# io-board-c-3.net
KiCad netlist of a schematic drawn in EAGLE
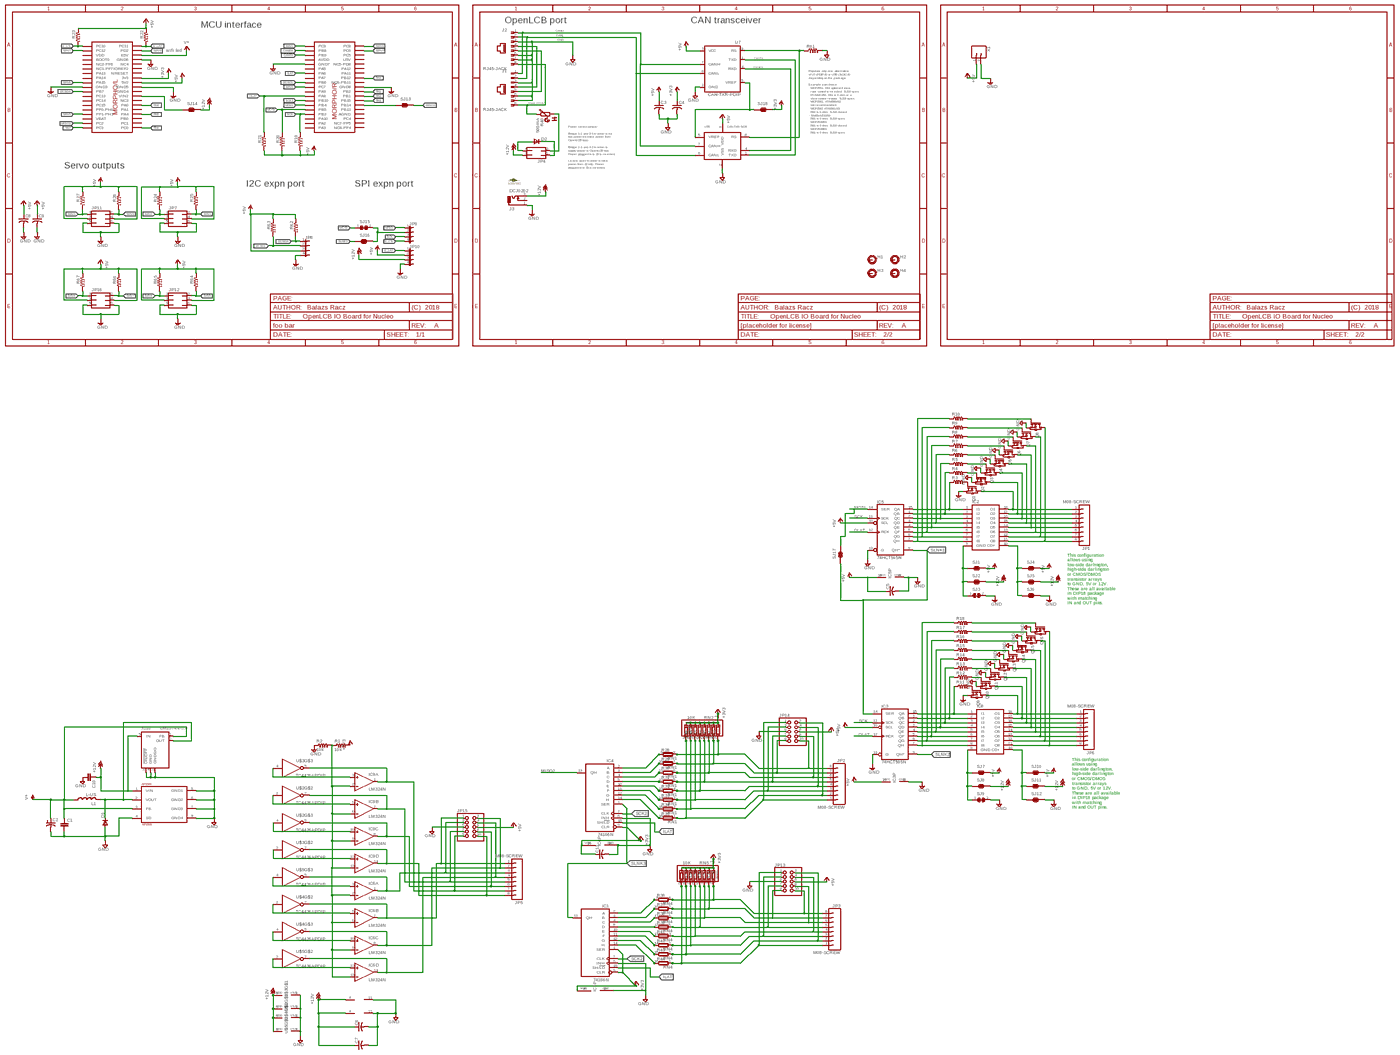
[diagram p0: schematic, sheet 1, overview]
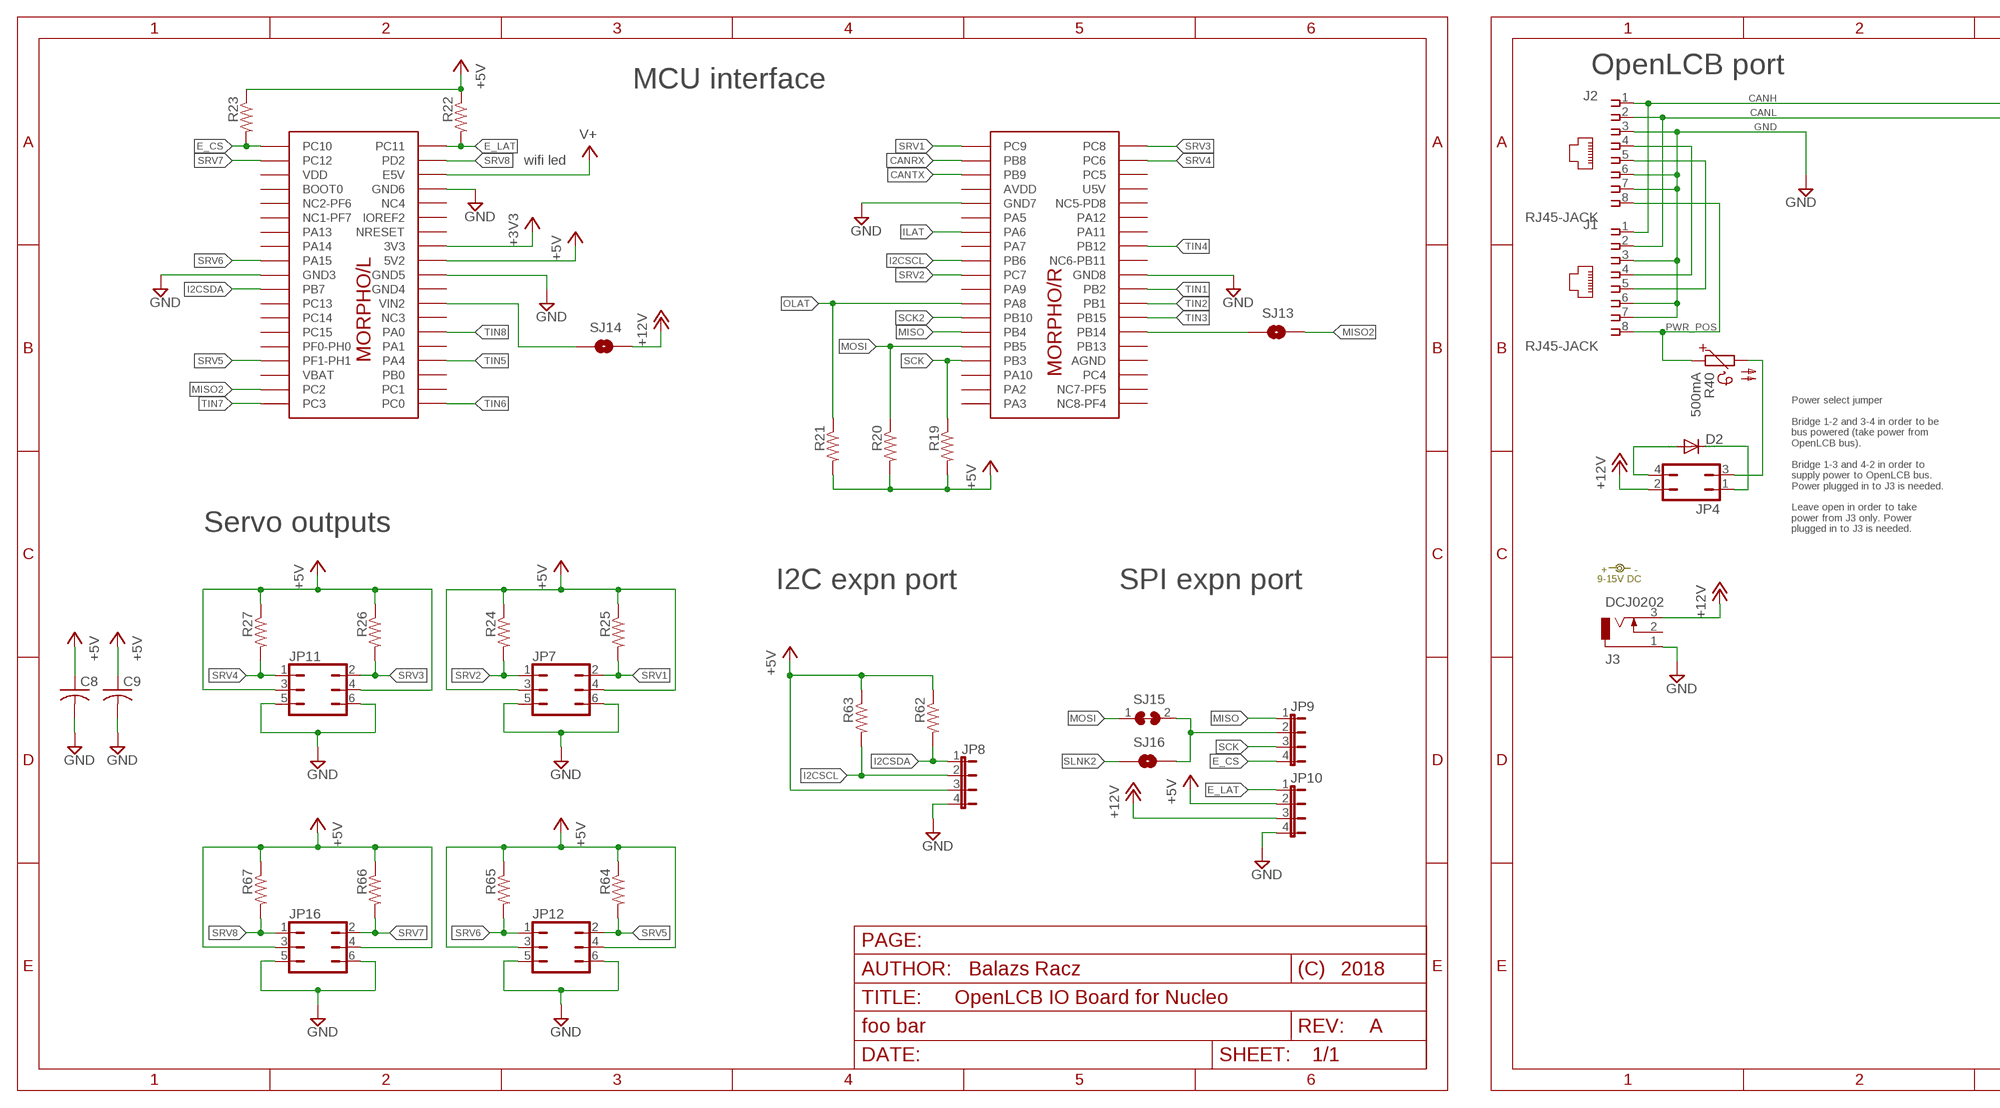
[diagram p1: schematic, sheet 1, part 1 of 4]
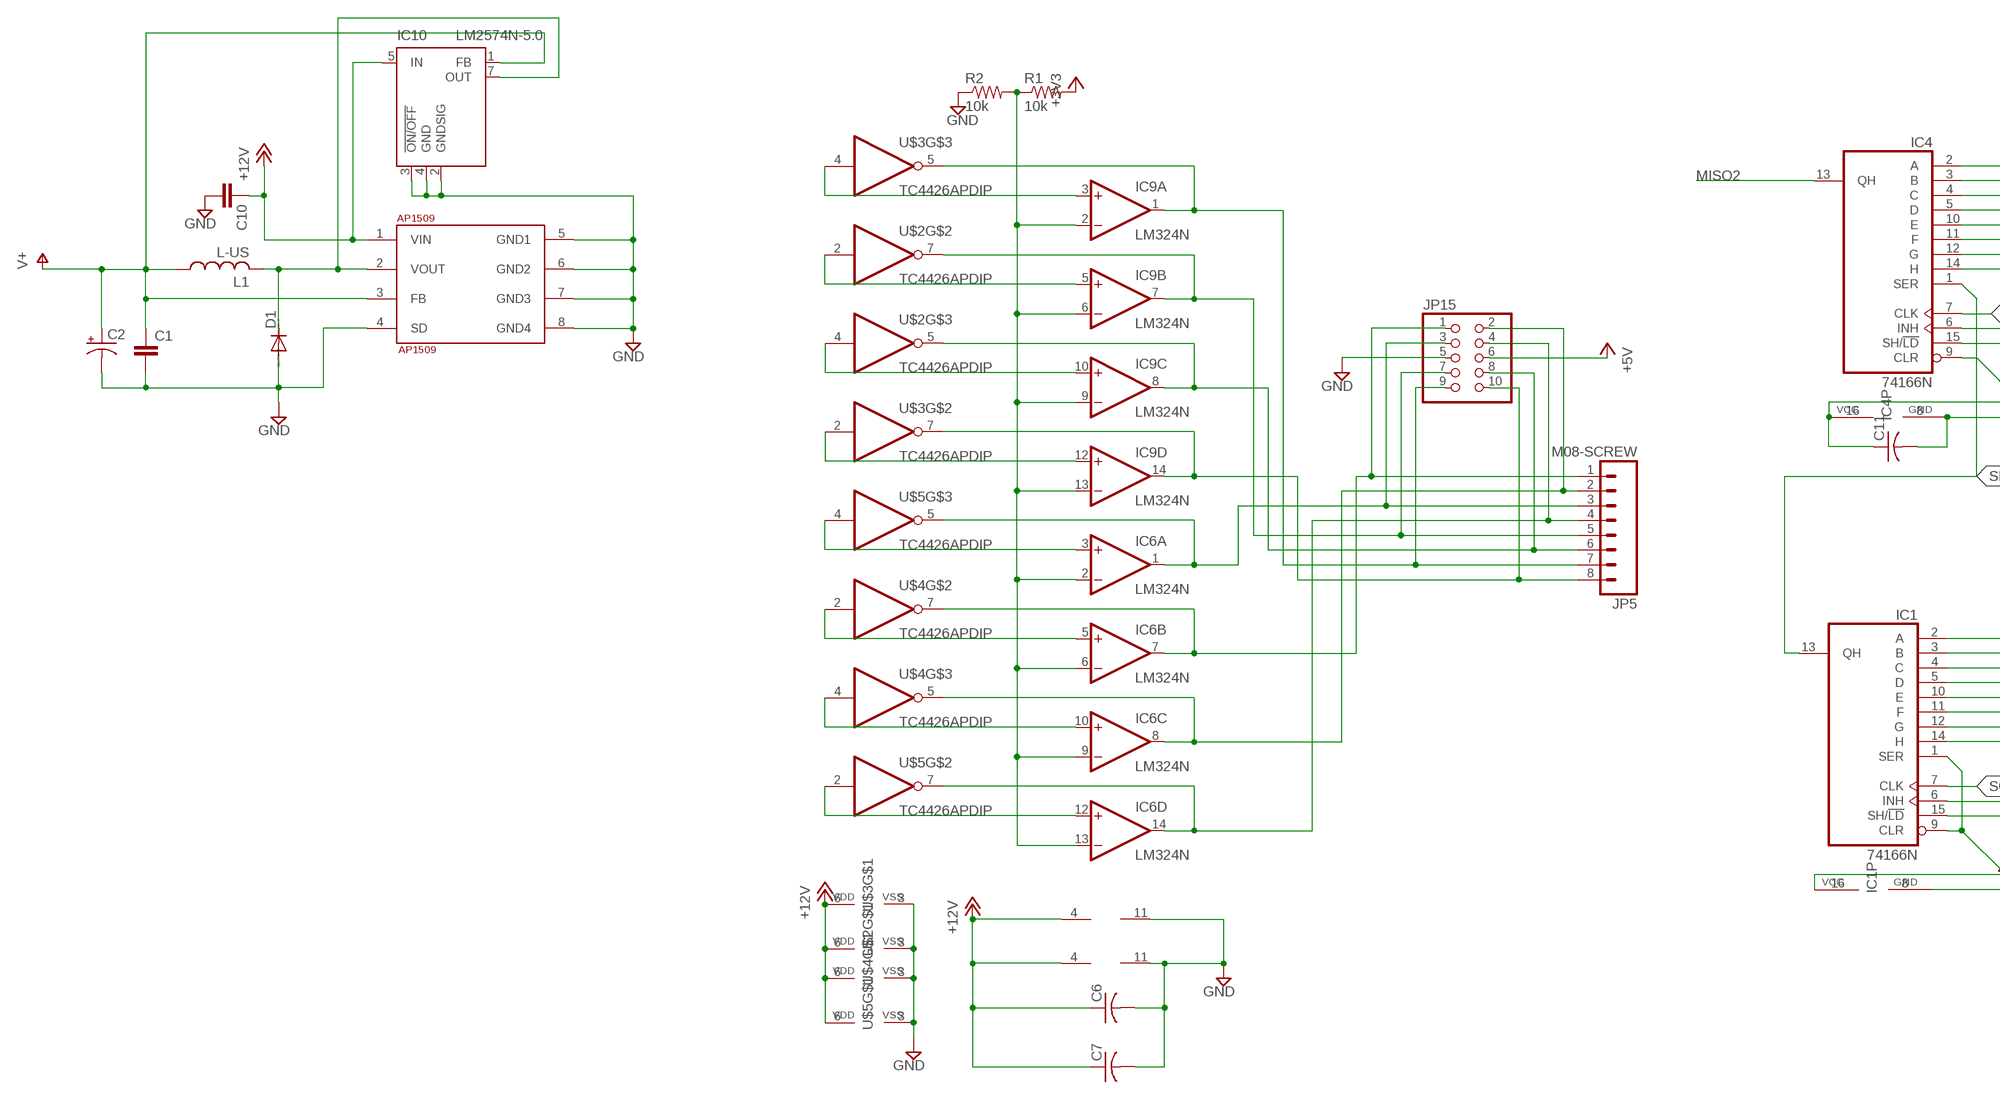
[diagram p2: schematic, sheet 1, part 2 of 4]
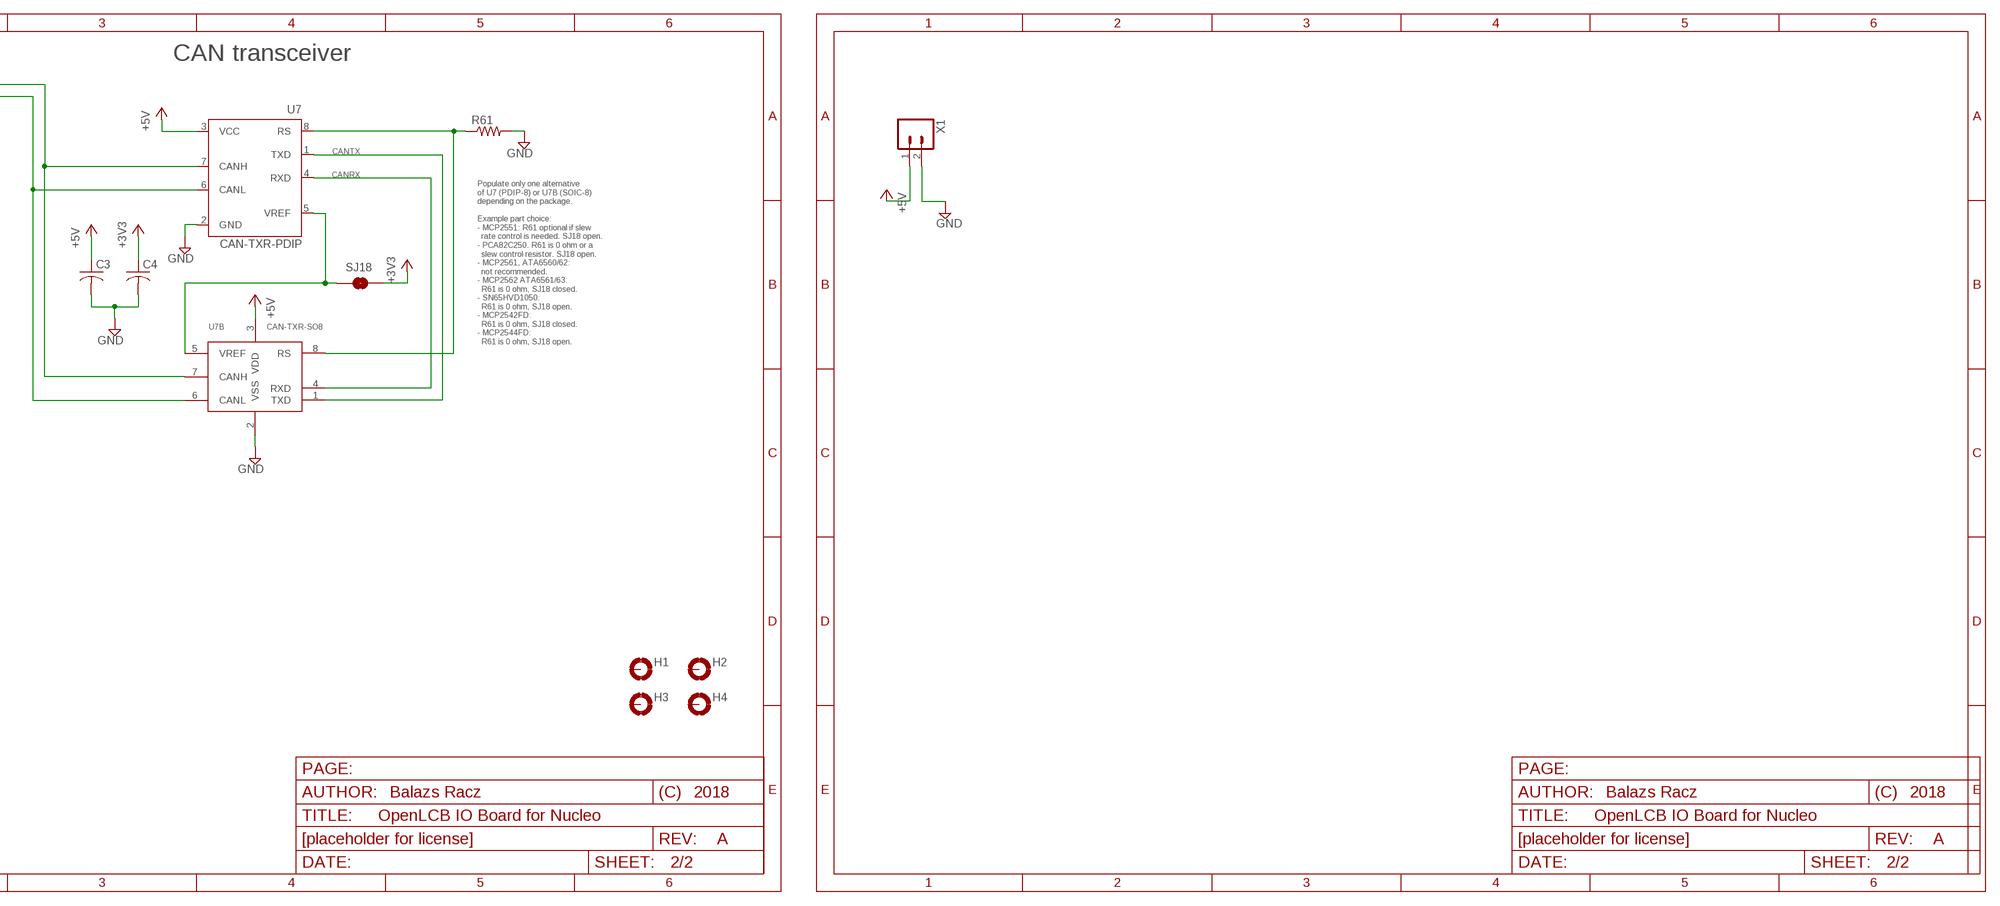
[diagram p3: schematic, sheet 1, part 3 of 4]
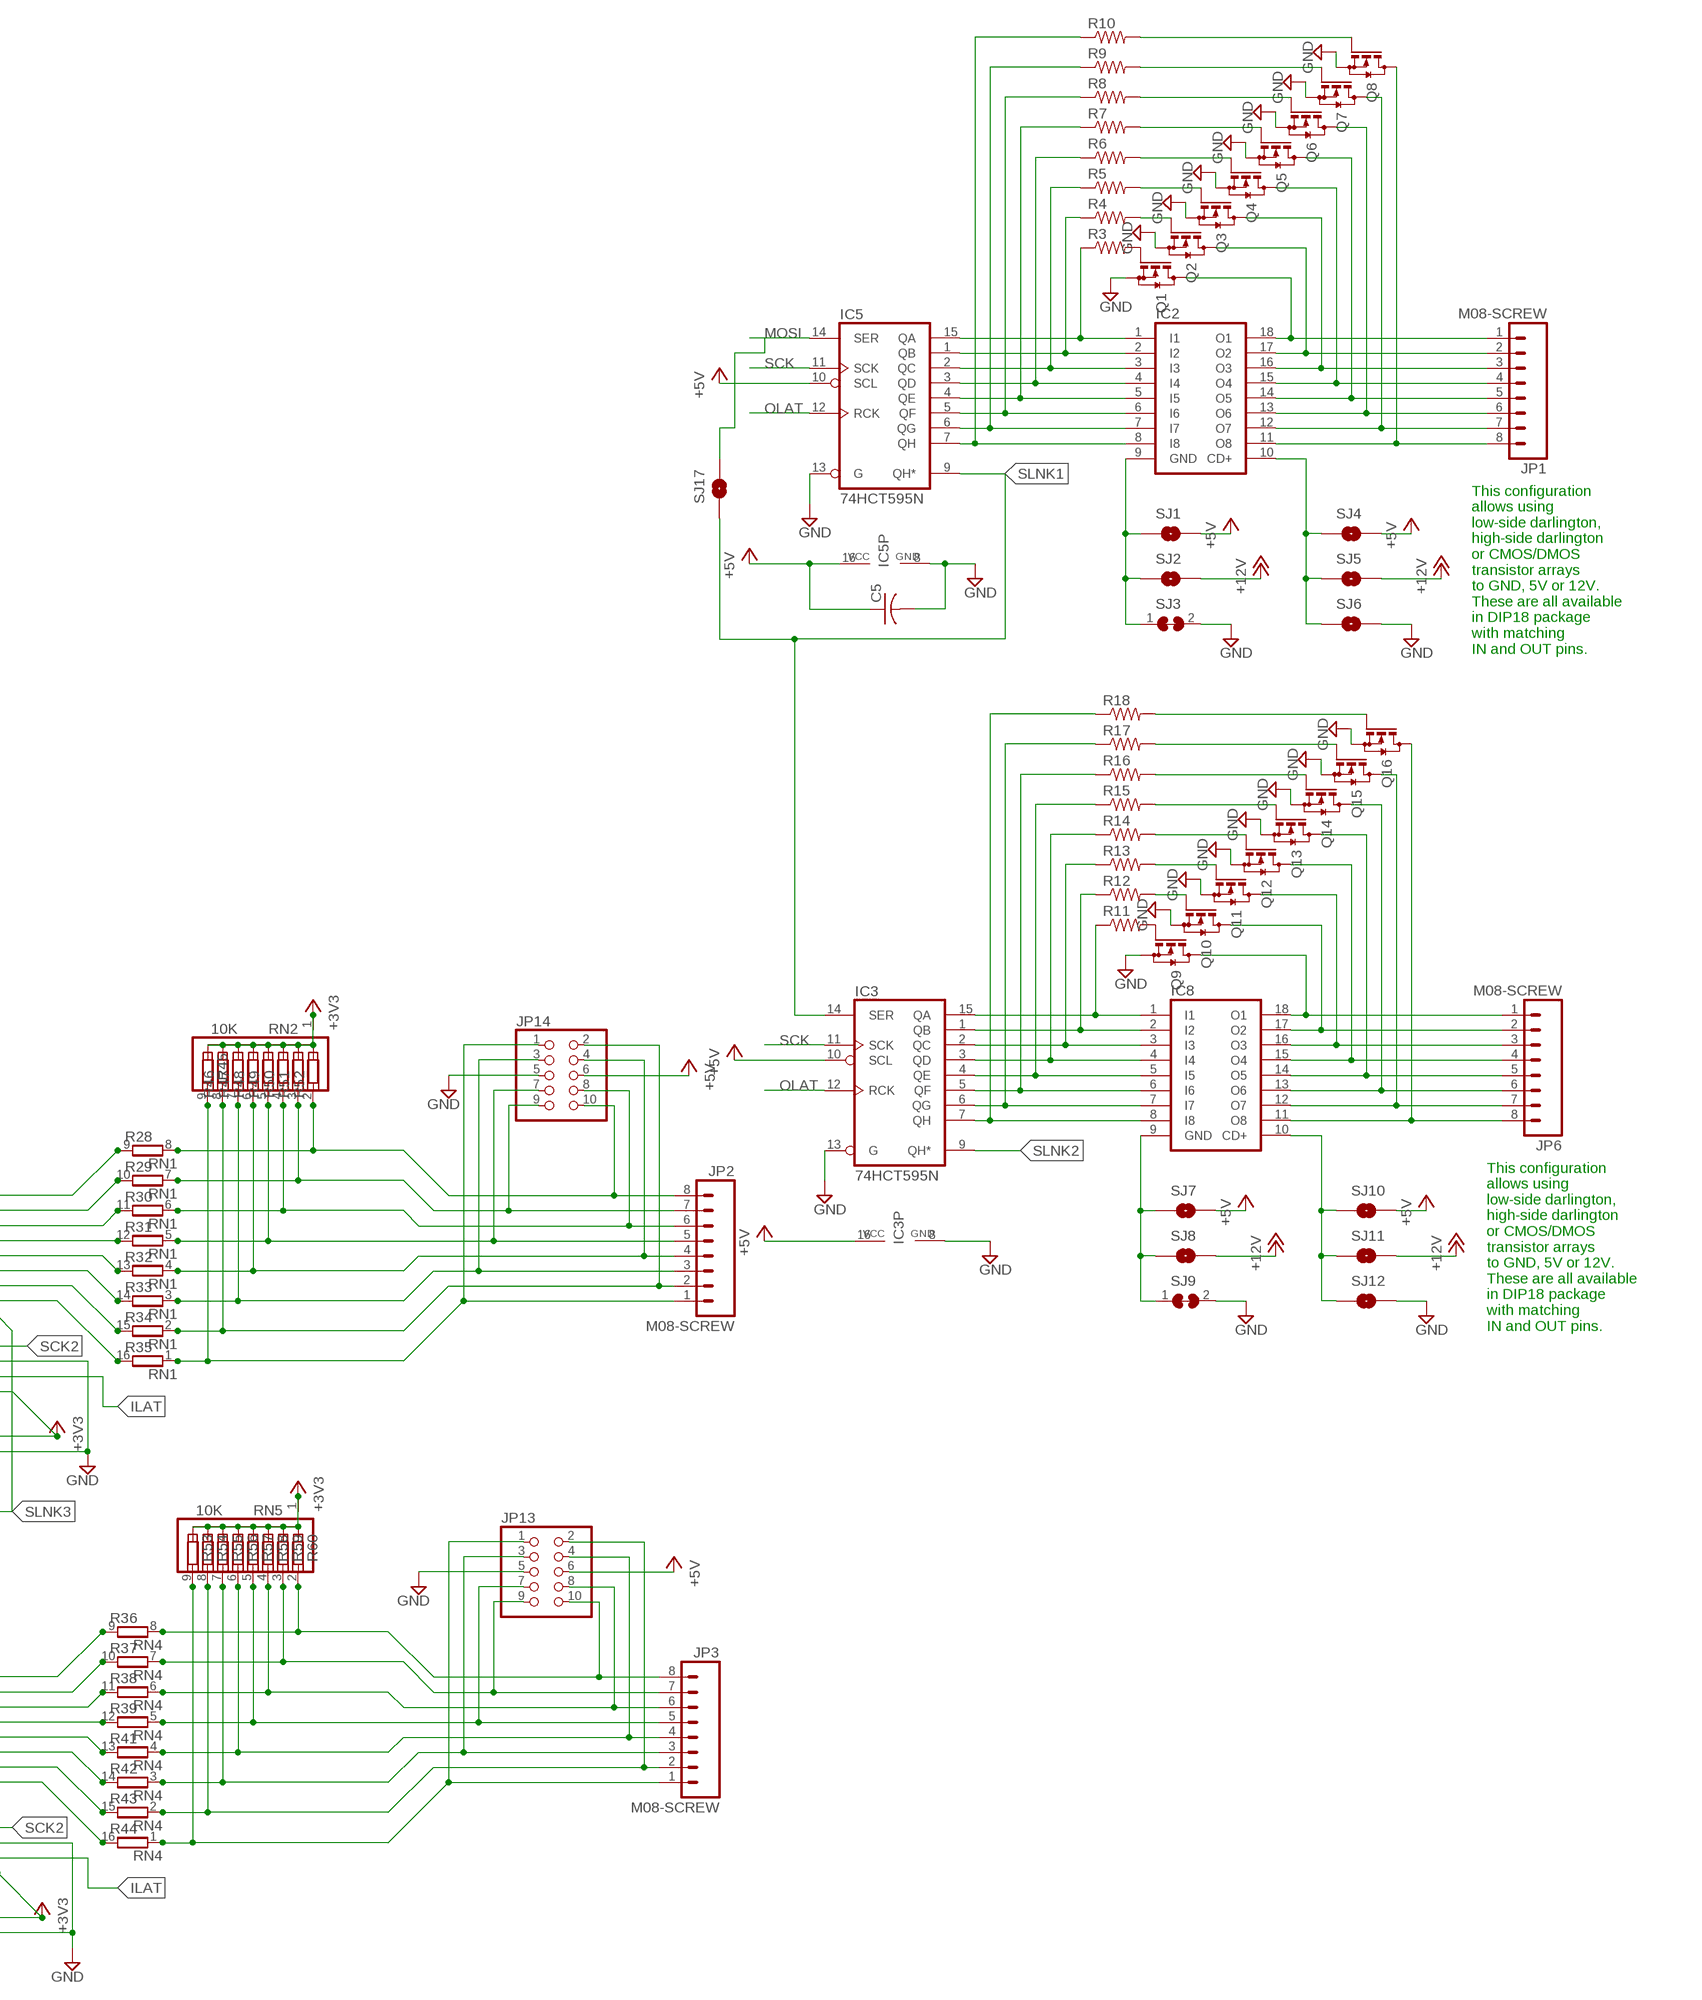
[diagram p4: schematic, sheet 1, part 4 of 4]

(export (version "E")
  (design (tool "Eeschema 10.0.6"))
  (components
    (comp (ref "+12V")
      (value "9-15V DC")
      (footprint "eagle-import:POWER_USAGE")
      (libsource (lib "eagle-import") (part "DOC-POWER_LABEL"))
    )
    (comp (ref "AP1509")
      (value "AP1509")
      (footprint "eagle-import:SO-08")
      (libsource (lib "eagle-import") (part "AP1509"))
    )
    (comp (ref "C1")
      (value "C-EUC1206")
      (footprint "eagle-import:C1206")
      (libsource (lib "eagle-import") (part "C-EUC1206"))
    )
    (comp (ref "C2")
      (value "CPOL-USE2.5-5")
      (footprint "eagle-import:E2,5-5")
      (libsource (lib "eagle-import") (part "CPOL-USE2.5-5"))
    )
    (comp (ref "C3")
      (value "C-USC0805")
      (footprint "eagle-import:C0805")
      (libsource (lib "eagle-import") (part "C-USC0805"))
    )
    (comp (ref "C4")
      (value "C-USC0805")
      (footprint "eagle-import:C0805")
      (libsource (lib "eagle-import") (part "C-USC0805"))
    )
    (comp (ref "C5")
      (value "C-USC0805")
      (footprint "eagle-import:C0805")
      (libsource (lib "eagle-import") (part "C-USC0805"))
    )
    (comp (ref "C6")
      (value "C-USC1206")
      (footprint "eagle-import:C1206")
      (libsource (lib "eagle-import") (part "C-USC1206"))
    )
    (comp (ref "C7")
      (value "C-USC1206")
      (footprint "eagle-import:C1206")
      (libsource (lib "eagle-import") (part "C-USC1206"))
    )
    (comp (ref "C8")
      (value "C-USC1206")
      (footprint "eagle-import:C1206")
      (libsource (lib "eagle-import") (part "C-USC1206"))
    )
    (comp (ref "C9")
      (value "C-USC1206")
      (footprint "eagle-import:C1206")
      (libsource (lib "eagle-import") (part "C-USC1206"))
    )
    (comp (ref "C10")
      (value "C-EUC1206")
      (footprint "eagle-import:C1206")
      (libsource (lib "eagle-import") (part "C-EUC1206"))
    )
    (comp (ref "C11")
      (value "C-USC0805")
      (footprint "eagle-import:C0805")
      (libsource (lib "eagle-import") (part "C-USC0805"))
    )
    (comp (ref "D1")
      (value "DIODE-DO41-7.6")
      (footprint "eagle-import:DO41-7.6")
      (libsource (lib "eagle-import") (part "DIODE-DO41-7.6"))
    )
    (comp (ref "D2")
      (value "DIODE-DO41-7.6")
      (footprint "eagle-import:DO41-7.6")
      (libsource (lib "eagle-import") (part "DIODE-DO41-7.6"))
    )
    (comp (ref "H1")
      (value "MOUNT-PAD-ROUND3.3")
      (footprint "eagle-import:3,3-PAD")
      (libsource (lib "eagle-import") (part "MOUNT-PAD-ROUND3.3"))
    )
    (comp (ref "H2")
      (value "MOUNT-PAD-ROUND3.3")
      (footprint "eagle-import:3,3-PAD")
      (libsource (lib "eagle-import") (part "MOUNT-PAD-ROUND3.3"))
    )
    (comp (ref "H3")
      (value "MOUNT-PAD-ROUND3.3")
      (footprint "eagle-import:3,3-PAD")
      (libsource (lib "eagle-import") (part "MOUNT-PAD-ROUND3.3"))
    )
    (comp (ref "H4")
      (value "MOUNT-PAD-ROUND3.3")
      (footprint "eagle-import:3,3-PAD")
      (libsource (lib "eagle-import") (part "MOUNT-PAD-ROUND3.3"))
    )
    (comp (ref "IC1")
      (value "74166N")
      (footprint "eagle-import:DIL16")
      (libsource (lib "eagle-import") (part "74166N"))
    )
    (comp (ref "IC2")
      (value "ULN2803A")
      (footprint "eagle-import:DIL18-THIN")
      (libsource (lib "eagle-import") (part "ULN2803A"))
    )
    (comp (ref "IC3")
      (value "74HCT595N")
      (footprint "eagle-import:DIL16")
      (libsource (lib "eagle-import") (part "74595NHCT"))
    )
    (comp (ref "IC4")
      (value "74166N")
      (footprint "eagle-import:DIL16")
      (libsource (lib "eagle-import") (part "74166N"))
    )
    (comp (ref "IC5")
      (value "74HCT595N")
      (footprint "eagle-import:DIL16")
      (libsource (lib "eagle-import") (part "74595NHCT"))
    )
    (comp (ref "IC6")
      (value "LM324N")
      (footprint "eagle-import:DIL14")
      (libsource (lib "eagle-import") (part "LM324N"))
    )
    (comp (ref "IC8")
      (value "ULN2803A")
      (footprint "eagle-import:DIL18-THIN")
      (libsource (lib "eagle-import") (part "ULN2803A"))
    )
    (comp (ref "IC9")
      (value "LM324N")
      (footprint "eagle-import:DIL14")
      (libsource (lib "eagle-import") (part "LM324N"))
    )
    (comp (ref "IC10")
      (value "LM2574N-5.0")
      (footprint "eagle-import:DIL08")
      (libsource (lib "eagle-import") (part "LM2574?-N5.0"))
    )
    (comp (ref "J1")
      (value "RJ45-JACK")
      (footprint "eagle-import:RJ45-PULSE-E5J88")
      (libsource (lib "eagle-import") (part "RJ45-JACKRJ45-PULSE-E5J00"))
    )
    (comp (ref "J2")
      (value "RJ45-JACK")
      (footprint "eagle-import:RJ45-PULSE-E5J88")
      (libsource (lib "eagle-import") (part "RJ45-JACKRJ45-PULSE-E5J00"))
    )
    (comp (ref "J3")
      (value "DCJ0202")
      (footprint "eagle-import:DCJ0202")
      (libsource (lib "eagle-import") (part "DCJ0202"))
    )
    (comp (ref "JP1")
      (value "M08-SCREW")
      (footprint "eagle-import:1X08_TERMINAL")
      (libsource (lib "eagle-import") (part "M08-SCREW"))
    )
    (comp (ref "JP2")
      (value "M08-SCREW")
      (footprint "eagle-import:1X08_TERMINAL")
      (libsource (lib "eagle-import") (part "M08-SCREW"))
    )
    (comp (ref "JP3")
      (value "M08-SCREW")
      (footprint "eagle-import:1X08_TERMINAL")
      (libsource (lib "eagle-import") (part "M08-SCREW"))
    )
    (comp (ref "JP4")
      (value "JP2Q")
      (footprint "eagle-import:JP2Q")
      (libsource (lib "eagle-import") (part "JP2Q"))
    )
    (comp (ref "JP5")
      (value "M08-SCREW")
      (footprint "eagle-import:1X08_TERMINAL")
      (libsource (lib "eagle-import") (part "M08-SCREW"))
    )
    (comp (ref "JP6")
      (value "M08-SCREW")
      (footprint "eagle-import:1X08_TERMINAL")
      (libsource (lib "eagle-import") (part "M08-SCREW"))
    )
    (comp (ref "JP7")
      (value "JP3Q")
      (footprint "eagle-import:JP3Q")
      (libsource (lib "eagle-import") (part "JP3Q"))
    )
    (comp (ref "JP8")
      (value "JP4-FLAT")
      (footprint "eagle-import:JP4F")
      (libsource (lib "eagle-import") (part "JP4-FLAT"))
    )
    (comp (ref "JP9")
      (value "JP4-FLAT")
      (footprint "eagle-import:JP4F")
      (libsource (lib "eagle-import") (part "JP4-FLAT"))
    )
    (comp (ref "JP10")
      (value "JP4-FLAT")
      (footprint "eagle-import:JP4F")
      (libsource (lib "eagle-import") (part "JP4-FLAT"))
    )
    (comp (ref "JP11")
      (value "JP3Q")
      (footprint "eagle-import:JP3Q")
      (libsource (lib "eagle-import") (part "JP3Q"))
    )
    (comp (ref "JP12")
      (value "JP3Q")
      (footprint "eagle-import:JP3Q")
      (libsource (lib "eagle-import") (part "JP3Q"))
    )
    (comp (ref "JP13")
      (value "PINHD-2X5CN")
      (footprint "eagle-import:CON10M")
      (libsource (lib "eagle-import") (part "PINHD-2X5CN"))
    )
    (comp (ref "JP14")
      (value "PINHD-2X5CN")
      (footprint "eagle-import:CON10M")
      (libsource (lib "eagle-import") (part "PINHD-2X5CN"))
    )
    (comp (ref "JP15")
      (value "PINHD-2X5CN")
      (footprint "eagle-import:CON10M")
      (libsource (lib "eagle-import") (part "PINHD-2X5CN"))
    )
    (comp (ref "JP16")
      (value "JP3Q")
      (footprint "eagle-import:JP3Q")
      (libsource (lib "eagle-import") (part "JP3Q"))
    )
    (comp (ref "L1")
      (value "L-US")
      (footprint "eagle-import:L5-8,5")
      (libsource (lib "eagle-import") (part "L-US"))
    )
    (comp (ref "Q1")
      (value "BSS123")
      (footprint "eagle-import:SOT23")
      (libsource (lib "eagle-import") (part "BSS123"))
    )
    (comp (ref "Q2")
      (value "BSS123")
      (footprint "eagle-import:SOT23")
      (libsource (lib "eagle-import") (part "BSS123"))
    )
    (comp (ref "Q3")
      (value "BSS123")
      (footprint "eagle-import:SOT23")
      (libsource (lib "eagle-import") (part "BSS123"))
    )
    (comp (ref "Q4")
      (value "BSS123")
      (footprint "eagle-import:SOT23")
      (libsource (lib "eagle-import") (part "BSS123"))
    )
    (comp (ref "Q5")
      (value "BSS123")
      (footprint "eagle-import:SOT23")
      (libsource (lib "eagle-import") (part "BSS123"))
    )
    (comp (ref "Q6")
      (value "BSS123")
      (footprint "eagle-import:SOT23")
      (libsource (lib "eagle-import") (part "BSS123"))
    )
    (comp (ref "Q7")
      (value "BSS123")
      (footprint "eagle-import:SOT23")
      (libsource (lib "eagle-import") (part "BSS123"))
    )
    (comp (ref "Q8")
      (value "BSS123")
      (footprint "eagle-import:SOT23")
      (libsource (lib "eagle-import") (part "BSS123"))
    )
    (comp (ref "Q9")
      (value "BSS123")
      (footprint "eagle-import:SOT23")
      (libsource (lib "eagle-import") (part "BSS123"))
    )
    (comp (ref "Q10")
      (value "BSS123")
      (footprint "eagle-import:SOT23")
      (libsource (lib "eagle-import") (part "BSS123"))
    )
    (comp (ref "Q11")
      (value "BSS123")
      (footprint "eagle-import:SOT23")
      (libsource (lib "eagle-import") (part "BSS123"))
    )
    (comp (ref "Q12")
      (value "BSS123")
      (footprint "eagle-import:SOT23")
      (libsource (lib "eagle-import") (part "BSS123"))
    )
    (comp (ref "Q13")
      (value "BSS123")
      (footprint "eagle-import:SOT23")
      (libsource (lib "eagle-import") (part "BSS123"))
    )
    (comp (ref "Q14")
      (value "BSS123")
      (footprint "eagle-import:SOT23")
      (libsource (lib "eagle-import") (part "BSS123"))
    )
    (comp (ref "Q15")
      (value "BSS123")
      (footprint "eagle-import:SOT23")
      (libsource (lib "eagle-import") (part "BSS123"))
    )
    (comp (ref "Q16")
      (value "BSS123")
      (footprint "eagle-import:SOT23")
      (libsource (lib "eagle-import") (part "BSS123"))
    )
    (comp (ref "R1")
      (value "10k")
      (footprint "eagle-import:R0805")
      (libsource (lib "eagle-import") (part "R-US_R0805"))
    )
    (comp (ref "R2")
      (value "10k")
      (footprint "eagle-import:R0805")
      (libsource (lib "eagle-import") (part "R-US_R0805"))
    )
    (comp (ref "R3")
      (value "R-US_R0603")
      (footprint "eagle-import:R0603")
      (libsource (lib "eagle-import") (part "R-US_R0603"))
    )
    (comp (ref "R4")
      (value "R-US_R0603")
      (footprint "eagle-import:R0603")
      (libsource (lib "eagle-import") (part "R-US_R0603"))
    )
    (comp (ref "R5")
      (value "R-US_R0603")
      (footprint "eagle-import:R0603")
      (libsource (lib "eagle-import") (part "R-US_R0603"))
    )
    (comp (ref "R6")
      (value "R-US_R0603")
      (footprint "eagle-import:R0603")
      (libsource (lib "eagle-import") (part "R-US_R0603"))
    )
    (comp (ref "R7")
      (value "R-US_R0603")
      (footprint "eagle-import:R0603")
      (libsource (lib "eagle-import") (part "R-US_R0603"))
    )
    (comp (ref "R8")
      (value "R-US_R0603")
      (footprint "eagle-import:R0603")
      (libsource (lib "eagle-import") (part "R-US_R0603"))
    )
    (comp (ref "R9")
      (value "R-US_R0603")
      (footprint "eagle-import:R0603")
      (libsource (lib "eagle-import") (part "R-US_R0603"))
    )
    (comp (ref "R10")
      (value "R-US_R0603")
      (footprint "eagle-import:R0603")
      (libsource (lib "eagle-import") (part "R-US_R0603"))
    )
    (comp (ref "R11")
      (value "R-US_R0603")
      (footprint "eagle-import:R0603")
      (libsource (lib "eagle-import") (part "R-US_R0603"))
    )
    (comp (ref "R12")
      (value "R-US_R0603")
      (footprint "eagle-import:R0603")
      (libsource (lib "eagle-import") (part "R-US_R0603"))
    )
    (comp (ref "R13")
      (value "R-US_R0603")
      (footprint "eagle-import:R0603")
      (libsource (lib "eagle-import") (part "R-US_R0603"))
    )
    (comp (ref "R14")
      (value "R-US_R0603")
      (footprint "eagle-import:R0603")
      (libsource (lib "eagle-import") (part "R-US_R0603"))
    )
    (comp (ref "R15")
      (value "R-US_R0603")
      (footprint "eagle-import:R0603")
      (libsource (lib "eagle-import") (part "R-US_R0603"))
    )
    (comp (ref "R16")
      (value "R-US_R0603")
      (footprint "eagle-import:R0603")
      (libsource (lib "eagle-import") (part "R-US_R0603"))
    )
    (comp (ref "R17")
      (value "R-US_R0603")
      (footprint "eagle-import:R0603")
      (libsource (lib "eagle-import") (part "R-US_R0603"))
    )
    (comp (ref "R18")
      (value "R-US_R0603")
      (footprint "eagle-import:R0603")
      (libsource (lib "eagle-import") (part "R-US_R0603"))
    )
    (comp (ref "R19")
      (value "R-US_R0805")
      (footprint "eagle-import:R0805")
      (libsource (lib "eagle-import") (part "rcl_334_R-US_R0805"))
    )
    (comp (ref "R20")
      (value "R-US_R0805")
      (footprint "eagle-import:R0805")
      (libsource (lib "eagle-import") (part "rcl_334_R-US_R0805"))
    )
    (comp (ref "R21")
      (value "R-US_R0805")
      (footprint "eagle-import:R0805")
      (libsource (lib "eagle-import") (part "rcl_334_R-US_R0805"))
    )
    (comp (ref "R22")
      (value "R-US_R0805")
      (footprint "eagle-import:R0805")
      (libsource (lib "eagle-import") (part "rcl_334_R-US_R0805"))
    )
    (comp (ref "R23")
      (value "R-US_R0805")
      (footprint "eagle-import:R0805")
      (libsource (lib "eagle-import") (part "rcl_334_R-US_R0805"))
    )
    (comp (ref "R24")
      (value "R-US_R0805")
      (footprint "eagle-import:R0805")
      (libsource (lib "eagle-import") (part "rcl_334_R-US_R0805"))
    )
    (comp (ref "R25")
      (value "R-US_R0805")
      (footprint "eagle-import:R0805")
      (libsource (lib "eagle-import") (part "rcl_334_R-US_R0805"))
    )
    (comp (ref "R26")
      (value "R-US_R0805")
      (footprint "eagle-import:R0805")
      (libsource (lib "eagle-import") (part "rcl_334_R-US_R0805"))
    )
    (comp (ref "R27")
      (value "R-US_R0805")
      (footprint "eagle-import:R0805")
      (libsource (lib "eagle-import") (part "rcl_334_R-US_R0805"))
    )
    (comp (ref "R28")
      (value "R-EU_R0603")
      (footprint "eagle-import:R0603")
      (libsource (lib "eagle-import") (part "R-EU_R0603"))
    )
    (comp (ref "R29")
      (value "R-EU_R0603")
      (footprint "eagle-import:R0603")
      (libsource (lib "eagle-import") (part "R-EU_R0603"))
    )
    (comp (ref "R30")
      (value "R-EU_R0603")
      (footprint "eagle-import:R0603")
      (libsource (lib "eagle-import") (part "R-EU_R0603"))
    )
    (comp (ref "R31")
      (value "R-EU_R0603")
      (footprint "eagle-import:R0603")
      (libsource (lib "eagle-import") (part "R-EU_R0603"))
    )
    (comp (ref "R32")
      (value "R-EU_R0603")
      (footprint "eagle-import:R0603")
      (libsource (lib "eagle-import") (part "R-EU_R0603"))
    )
    (comp (ref "R33")
      (value "R-EU_R0603")
      (footprint "eagle-import:R0603")
      (libsource (lib "eagle-import") (part "R-EU_R0603"))
    )
    (comp (ref "R34")
      (value "R-EU_R0603")
      (footprint "eagle-import:R0603")
      (libsource (lib "eagle-import") (part "R-EU_R0603"))
    )
    (comp (ref "R35")
      (value "R-EU_R0603")
      (footprint "eagle-import:R0603")
      (libsource (lib "eagle-import") (part "R-EU_R0603"))
    )
    (comp (ref "R36")
      (value "R-EU_R0603")
      (footprint "eagle-import:R0603")
      (libsource (lib "eagle-import") (part "R-EU_R0603"))
    )
    (comp (ref "R37")
      (value "R-EU_R0603")
      (footprint "eagle-import:R0603")
      (libsource (lib "eagle-import") (part "R-EU_R0603"))
    )
    (comp (ref "R38")
      (value "R-EU_R0603")
      (footprint "eagle-import:R0603")
      (libsource (lib "eagle-import") (part "R-EU_R0603"))
    )
    (comp (ref "R39")
      (value "R-EU_R0603")
      (footprint "eagle-import:R0603")
      (libsource (lib "eagle-import") (part "R-EU_R0603"))
    )
    (comp (ref "R40")
      (value "500mA")
      (footprint "eagle-import:PTC1812")
      (libsource (lib "eagle-import") (part "PTC_1812"))
    )
    (comp (ref "R41")
      (value "R-EU_R0603")
      (footprint "eagle-import:R0603")
      (libsource (lib "eagle-import") (part "R-EU_R0603"))
    )
    (comp (ref "R42")
      (value "R-EU_R0603")
      (footprint "eagle-import:R0603")
      (libsource (lib "eagle-import") (part "R-EU_R0603"))
    )
    (comp (ref "R43")
      (value "R-EU_R0603")
      (footprint "eagle-import:R0603")
      (libsource (lib "eagle-import") (part "R-EU_R0603"))
    )
    (comp (ref "R44")
      (value "R-EU_R0603")
      (footprint "eagle-import:R0603")
      (libsource (lib "eagle-import") (part "R-EU_R0603"))
    )
    (comp (ref "R45")
      (value "R-EU_R0603")
      (footprint "eagle-import:R0603")
      (libsource (lib "eagle-import") (part "R-EU_R0603"))
    )
    (comp (ref "R46")
      (value "R-EU_R0603")
      (footprint "eagle-import:R0603")
      (libsource (lib "eagle-import") (part "R-EU_R0603"))
    )
    (comp (ref "R47")
      (value "R-EU_R0603")
      (footprint "eagle-import:R0603")
      (libsource (lib "eagle-import") (part "R-EU_R0603"))
    )
    (comp (ref "R48")
      (value "R-EU_R0603")
      (footprint "eagle-import:R0603")
      (libsource (lib "eagle-import") (part "R-EU_R0603"))
    )
    (comp (ref "R49")
      (value "R-EU_R0603")
      (footprint "eagle-import:R0603")
      (libsource (lib "eagle-import") (part "R-EU_R0603"))
    )
    (comp (ref "R50")
      (value "R-EU_R0603")
      (footprint "eagle-import:R0603")
      (libsource (lib "eagle-import") (part "R-EU_R0603"))
    )
    (comp (ref "R51")
      (value "R-EU_R0603")
      (footprint "eagle-import:R0603")
      (libsource (lib "eagle-import") (part "R-EU_R0603"))
    )
    (comp (ref "R52")
      (value "R-EU_R0603")
      (footprint "eagle-import:R0603")
      (libsource (lib "eagle-import") (part "R-EU_R0603"))
    )
    (comp (ref "R53")
      (value "R-EU_R0603")
      (footprint "eagle-import:R0603")
      (libsource (lib "eagle-import") (part "R-EU_R0603"))
    )
    (comp (ref "R54")
      (value "R-EU_R0603")
      (footprint "eagle-import:R0603")
      (libsource (lib "eagle-import") (part "R-EU_R0603"))
    )
    (comp (ref "R55")
      (value "R-EU_R0603")
      (footprint "eagle-import:R0603")
      (libsource (lib "eagle-import") (part "R-EU_R0603"))
    )
    (comp (ref "R56")
      (value "R-EU_R0603")
      (footprint "eagle-import:R0603")
      (libsource (lib "eagle-import") (part "R-EU_R0603"))
    )
    (comp (ref "R57")
      (value "R-EU_R0603")
      (footprint "eagle-import:R0603")
      (libsource (lib "eagle-import") (part "R-EU_R0603"))
    )
    (comp (ref "R58")
      (value "R-EU_R0603")
      (footprint "eagle-import:R0603")
      (libsource (lib "eagle-import") (part "R-EU_R0603"))
    )
    (comp (ref "R59")
      (value "R-EU_R0603")
      (footprint "eagle-import:R0603")
      (libsource (lib "eagle-import") (part "R-EU_R0603"))
    )
    (comp (ref "R60")
      (value "R-EU_R0603")
      (footprint "eagle-import:R0603")
      (libsource (lib "eagle-import") (part "R-EU_R0603"))
    )
    (comp (ref "R61")
      (value "R-US_R0805")
      (footprint "eagle-import:R0805")
      (libsource (lib "eagle-import") (part "rcl_334_R-US_R0805"))
    )
    (comp (ref "R62")
      (value "R-US_R0805")
      (footprint "eagle-import:R0805")
      (libsource (lib "eagle-import") (part "rcl_334_R-US_R0805"))
    )
    (comp (ref "R63")
      (value "R-US_R0805")
      (footprint "eagle-import:R0805")
      (libsource (lib "eagle-import") (part "rcl_334_R-US_R0805"))
    )
    (comp (ref "R64")
      (value "R-US_R0805")
      (footprint "eagle-import:R0805")
      (libsource (lib "eagle-import") (part "rcl_334_R-US_R0805"))
    )
    (comp (ref "R65")
      (value "R-US_R0805")
      (footprint "eagle-import:R0805")
      (libsource (lib "eagle-import") (part "rcl_334_R-US_R0805"))
    )
    (comp (ref "R66")
      (value "R-US_R0805")
      (footprint "eagle-import:R0805")
      (libsource (lib "eagle-import") (part "rcl_334_R-US_R0805"))
    )
    (comp (ref "R67")
      (value "R-US_R0805")
      (footprint "eagle-import:R0805")
      (libsource (lib "eagle-import") (part "rcl_334_R-US_R0805"))
    )
    (comp (ref "RN1")
      (value "8R-P")
      (footprint "eagle-import:DIL16")
      (libsource (lib "eagle-import") (part "8R-P"))
    )
    (comp (ref "RN2")
      (value "10K")
      (footprint "eagle-import:SIL9")
      (libsource (lib "eagle-import") (part "G08R"))
    )
    (comp (ref "RN4")
      (value "8R-P")
      (footprint "eagle-import:DIL16")
      (libsource (lib "eagle-import") (part "8R-P"))
    )
    (comp (ref "RN5")
      (value "10K")
      (footprint "eagle-import:SIL9")
      (libsource (lib "eagle-import") (part "G08R"))
    )
    (comp (ref "SJ1")
      (value "SJRND2")
      (footprint "eagle-import:SJ_RND2")
      (libsource (lib "eagle-import") (part "SJRND2"))
    )
    (comp (ref "SJ2")
      (value "SJRND2")
      (footprint "eagle-import:SJ_RND2")
      (libsource (lib "eagle-import") (part "SJRND2"))
    )
    (comp (ref "SJ3")
      (value "SJ-C")
      (footprint "eagle-import:SJW-C")
      (libsource (lib "eagle-import") (part "SJ-C"))
    )
    (comp (ref "SJ4")
      (value "SJRND2")
      (footprint "eagle-import:SJ_RND2")
      (libsource (lib "eagle-import") (part "SJRND2"))
    )
    (comp (ref "SJ5")
      (value "SJRND2")
      (footprint "eagle-import:SJ_RND2")
      (libsource (lib "eagle-import") (part "SJRND2"))
    )
    (comp (ref "SJ6")
      (value "SJRND2")
      (footprint "eagle-import:SJ_RND2")
      (libsource (lib "eagle-import") (part "SJRND2"))
    )
    (comp (ref "SJ7")
      (value "SJRND2")
      (footprint "eagle-import:SJ_RND2")
      (libsource (lib "eagle-import") (part "SJRND2"))
    )
    (comp (ref "SJ8")
      (value "SJRND2")
      (footprint "eagle-import:SJ_RND2")
      (libsource (lib "eagle-import") (part "SJRND2"))
    )
    (comp (ref "SJ9")
      (value "SJ-C")
      (footprint "eagle-import:SJW-C")
      (libsource (lib "eagle-import") (part "SJ-C"))
    )
    (comp (ref "SJ10")
      (value "SJRND2")
      (footprint "eagle-import:SJ_RND2")
      (libsource (lib "eagle-import") (part "SJRND2"))
    )
    (comp (ref "SJ11")
      (value "SJRND2")
      (footprint "eagle-import:SJ_RND2")
      (libsource (lib "eagle-import") (part "SJRND2"))
    )
    (comp (ref "SJ12")
      (value "SJRND2")
      (footprint "eagle-import:SJ_RND2")
      (libsource (lib "eagle-import") (part "SJRND2"))
    )
    (comp (ref "SJ13")
      (value "SJRND2")
      (footprint "eagle-import:SJ_RND2")
      (libsource (lib "eagle-import") (part "SJRND2"))
    )
    (comp (ref "SJ14")
      (value "SJRND2")
      (footprint "eagle-import:SJ_RND2")
      (libsource (lib "eagle-import") (part "SJRND2"))
    )
    (comp (ref "SJ15")
      (value "SJ-C")
      (footprint "eagle-import:SJW-C")
      (libsource (lib "eagle-import") (part "SJ-C"))
    )
    (comp (ref "SJ16")
      (value "SJRND2")
      (footprint "eagle-import:SJ_RND2")
      (libsource (lib "eagle-import") (part "SJRND2"))
    )
    (comp (ref "SJ17")
      (value "SJRND2")
      (footprint "eagle-import:SJ_RND2")
      (libsource (lib "eagle-import") (part "SJRND2"))
    )
    (comp (ref "SJ18")
      (value "SJRND2")
      (footprint "eagle-import:SJ_RND2")
      (libsource (lib "eagle-import") (part "SJRND2"))
    )
    (comp (ref "U$1")
      (value "NUCLEO_64_GENERIC")
      (footprint "eagle-import:NUCLEO_BRD_BASE64")
      (libsource (lib "eagle-import") (part "NUCLEO_64_GENERIC"))
    )
    (comp (ref "U$2")
      (value "TC4426APDIP")
      (footprint "eagle-import:DIL08-LONG")
      (libsource (lib "eagle-import") (part "TC4426APDIP"))
    )
    (comp (ref "U$3")
      (value "TC4426APDIP")
      (footprint "eagle-import:DIL08-LONG")
      (libsource (lib "eagle-import") (part "TC4426APDIP"))
    )
    (comp (ref "U$4")
      (value "TC4426APDIP")
      (footprint "eagle-import:DIL08-LONG")
      (libsource (lib "eagle-import") (part "TC4426APDIP"))
    )
    (comp (ref "U$5")
      (value "TC4426APDIP")
      (footprint "eagle-import:DIL08-LONG")
      (libsource (lib "eagle-import") (part "TC4426APDIP"))
    )
    (comp (ref "U7")
      (value "CAN-TXR-PDIP")
      (footprint "eagle-import:DIL08")
      (libsource (lib "eagle-import") (part "PCA82C250"))
    )
    (comp (ref "U7B")
      (value "CAN-TXR-SO8")
      (footprint "eagle-import:SO-08")
      (libsource (lib "eagle-import") (part "MCP2551-SN"))
    )
    (comp (ref "X1")
      (value "CONNECTOR-M023.5MM-LOCK")
      (footprint "eagle-import:SCREWTERMINAL-3.5MM-2_LOCK")
      (libsource (lib "eagle-import") (part "CONNECTOR-M023.5MM-LOCK"))
    )
  )
  (nets
    (net (code "1") (name "+3V3") (class "Default")
      (node (ref "C11") (pin "1") (pinfunction "1_1") (pintype "passive"))
      (node (ref "C4") (pin "1") (pinfunction "1_1") (pintype "passive"))
      (node (ref "IC1") (pin "1") (pinfunction "SER_1") (pintype "input"))
      (node (ref "IC1") (pin "16") (pinfunction "VCC_16") (pintype "power_in"))
      (node (ref "IC1") (pin "9") (pinfunction "CLR_9") (pintype "input"))
      (node (ref "IC4") (pin "16") (pinfunction "VCC_16") (pintype "power_in"))
      (node (ref "IC4") (pin "9") (pinfunction "CLR_9") (pintype "input"))
      (node (ref "R1") (pin "2") (pinfunction "2_2") (pintype "passive"))
      (node (ref "R45") (pin "1") (pinfunction "1_1") (pintype "passive"))
      (node (ref "R46") (pin "2") (pinfunction "2_2") (pintype "passive"))
      (node (ref "R47") (pin "2") (pinfunction "2_2") (pintype "passive"))
      (node (ref "R48") (pin "2") (pinfunction "2_2") (pintype "passive"))
      (node (ref "R49") (pin "2") (pinfunction "2_2") (pintype "passive"))
      (node (ref "R50") (pin "2") (pinfunction "2_2") (pintype "passive"))
      (node (ref "R51") (pin "2") (pinfunction "2_2") (pintype "passive"))
      (node (ref "R52") (pin "2") (pinfunction "2_2") (pintype "passive"))
      (node (ref "R53") (pin "1") (pinfunction "1_1") (pintype "passive"))
      (node (ref "R54") (pin "1") (pinfunction "1_1") (pintype "passive"))
      (node (ref "R55") (pin "1") (pinfunction "1_1") (pintype "passive"))
      (node (ref "R56") (pin "1") (pinfunction "1_1") (pintype "passive"))
      (node (ref "R57") (pin "1") (pinfunction "1_1") (pintype "passive"))
      (node (ref "R58") (pin "1") (pinfunction "1_1") (pintype "passive"))
      (node (ref "R59") (pin "1") (pinfunction "1_1") (pintype "passive"))
      (node (ref "R60") (pin "1") (pinfunction "1_1") (pintype "passive"))
      (node (ref "RN2") (pin "1") (pinfunction "1_1") (pintype "passive"))
      (node (ref "RN5") (pin "1") (pinfunction "1_1") (pintype "passive"))
      (node (ref "SJ18") (pin "P$1") (pinfunction "1_P$1") (pintype "passive"))
      (node (ref "U$1") (pin "3V3") (pinfunction "3V3_3V3") (pintype "power_in"))
    )
    (net (code "2") (name "+5V") (class "Default")
      (node (ref "C3") (pin "1") (pinfunction "1_1") (pintype "passive"))
      (node (ref "C5") (pin "1") (pinfunction "1_1") (pintype "passive"))
      (node (ref "C8") (pin "1") (pinfunction "1_1") (pintype "passive"))
      (node (ref "C9") (pin "1") (pinfunction "1_1") (pintype "passive"))
      (node (ref "IC3") (pin "10") (pinfunction "SCL_10") (pintype "input"))
      (node (ref "IC3") (pin "16") (pinfunction "VCC_16") (pintype "power_in"))
      (node (ref "IC5") (pin "10") (pinfunction "SCL_10") (pintype "input"))
      (node (ref "IC5") (pin "16") (pinfunction "VCC_16") (pintype "power_in"))
      (node (ref "JP10") (pin "2") (pinfunction "2_2") (pintype "passive"))
      (node (ref "JP11") (pin "3") (pinfunction "3_3") (pintype "passive"))
      (node (ref "JP11") (pin "4") (pinfunction "4_4") (pintype "passive"))
      (node (ref "JP12") (pin "3") (pinfunction "3_3") (pintype "passive"))
      (node (ref "JP12") (pin "4") (pinfunction "4_4") (pintype "passive"))
      (node (ref "JP13") (pin "6") (pinfunction "6_6") (pintype "passive"))
      (node (ref "JP14") (pin "6") (pinfunction "6_6") (pintype "passive"))
      (node (ref "JP15") (pin "6") (pinfunction "6_6") (pintype "passive"))
      (node (ref "JP16") (pin "3") (pinfunction "3_3") (pintype "passive"))
      (node (ref "JP16") (pin "4") (pinfunction "4_4") (pintype "passive"))
      (node (ref "JP7") (pin "3") (pinfunction "3_3") (pintype "passive"))
      (node (ref "JP7") (pin "4") (pinfunction "4_4") (pintype "passive"))
      (node (ref "JP8") (pin "3") (pinfunction "3_3") (pintype "passive"))
      (node (ref "R19") (pin "2") (pinfunction "2_2") (pintype "passive"))
      (node (ref "R20") (pin "2") (pinfunction "2_2") (pintype "passive"))
      (node (ref "R21") (pin "2") (pinfunction "2_2") (pintype "passive"))
      (node (ref "R22") (pin "1") (pinfunction "1_1") (pintype "passive"))
      (node (ref "R23") (pin "1") (pinfunction "1_1") (pintype "passive"))
      (node (ref "R24") (pin "1") (pinfunction "1_1") (pintype "passive"))
      (node (ref "R25") (pin "1") (pinfunction "1_1") (pintype "passive"))
      (node (ref "R26") (pin "1") (pinfunction "1_1") (pintype "passive"))
      (node (ref "R27") (pin "1") (pinfunction "1_1") (pintype "passive"))
      (node (ref "R62") (pin "1") (pinfunction "1_1") (pintype "passive"))
      (node (ref "R63") (pin "1") (pinfunction "1_1") (pintype "passive"))
      (node (ref "R64") (pin "1") (pinfunction "1_1") (pintype "passive"))
      (node (ref "R65") (pin "1") (pinfunction "1_1") (pintype "passive"))
      (node (ref "R66") (pin "1") (pinfunction "1_1") (pintype "passive"))
      (node (ref "R67") (pin "1") (pinfunction "1_1") (pintype "passive"))
      (node (ref "SJ1") (pin "P$2") (pinfunction "2_P$2") (pintype "passive"))
      (node (ref "SJ10") (pin "P$2") (pinfunction "2_P$2") (pintype "passive"))
      (node (ref "SJ4") (pin "P$2") (pinfunction "2_P$2") (pintype "passive"))
      (node (ref "SJ7") (pin "P$2") (pinfunction "2_P$2") (pintype "passive"))
      (node (ref "U$1") (pin "5V2") (pinfunction "5V2_5V2") (pintype "power_in"))
      (node (ref "U7") (pin "3") (pinfunction "VCC_3") (pintype "power_in"))
      (node (ref "U7B") (pin "3") (pinfunction "VDD_3") (pintype "power_in"))
      (node (ref "X1") (pin "1") (pinfunction "1_1") (pintype "passive"))
    )
    (net (code "3") (name "+12V") (class "Default")
      (node (ref "AP1509") (pin "1") (pinfunction "VIN_1") (pintype "bidirectional"))
      (node (ref "C10") (pin "1") (pinfunction "1_1") (pintype "passive"))
      (node (ref "C6") (pin "1") (pinfunction "1_1") (pintype "passive"))
      (node (ref "C7") (pin "1") (pinfunction "1_1") (pintype "passive"))
      (node (ref "IC10") (pin "5") (pinfunction "IN_5") (pintype "input"))
      (node (ref "IC6") (pin "4") (pinfunction "V+_4") (pintype "power_in"))
      (node (ref "IC9") (pin "4") (pinfunction "V+_4") (pintype "power_in"))
      (node (ref "J3") (pin "3") (pinfunction "3_3") (pintype "passive"))
      (node (ref "JP10") (pin "3") (pinfunction "3_3") (pintype "passive"))
      (node (ref "JP4") (pin "2") (pinfunction "2_2") (pintype "passive"))
      (node (ref "SJ11") (pin "P$2") (pinfunction "2_P$2") (pintype "passive"))
      (node (ref "SJ14") (pin "P$2") (pinfunction "2_P$2") (pintype "passive"))
      (node (ref "SJ2") (pin "P$2") (pinfunction "2_P$2") (pintype "passive"))
      (node (ref "SJ5") (pin "P$2") (pinfunction "2_P$2") (pintype "passive"))
      (node (ref "SJ8") (pin "P$2") (pinfunction "2_P$2") (pintype "passive"))
      (node (ref "U$2") (pin "6") (pinfunction "VDD_6") (pintype "power_in"))
      (node (ref "U$3") (pin "6") (pinfunction "VDD_6") (pintype "power_in"))
      (node (ref "U$4") (pin "6") (pinfunction "VDD_6") (pintype "power_in"))
      (node (ref "U$5") (pin "6") (pinfunction "VDD_6") (pintype "power_in"))
    )
    (net (code "4") (name "/AGND") (class "Default")
      (node (ref "U$1") (pin "AGND") (pinfunction "AGND_AGND") (pintype "power_in"))
    )
    (net (code "5") (name "/AVDD") (class "Default")
      (node (ref "U$1") (pin "AVDD") (pinfunction "AVDD_AVDD") (pintype "power_in"))
    )
    (net (code "6") (name "/CANH") (class "Default")
      (node (ref "J1") (pin "1") (pinfunction "1_1") (pintype "passive"))
      (node (ref "J2") (pin "1") (pinfunction "1_1") (pintype "passive"))
      (node (ref "U7") (pin "7") (pinfunction "CANH_7") (pintype "bidirectional"))
      (node (ref "U7B") (pin "7") (pinfunction "CANH_7") (pintype "bidirectional"))
    )
    (net (code "7") (name "/CANL") (class "Default")
      (node (ref "J1") (pin "2") (pinfunction "2_2") (pintype "passive"))
      (node (ref "J2") (pin "2") (pinfunction "2_2") (pintype "passive"))
      (node (ref "U7") (pin "6") (pinfunction "CANL_6") (pintype "bidirectional"))
      (node (ref "U7B") (pin "6") (pinfunction "CANL_6") (pintype "bidirectional"))
    )
    (net (code "8") (name "/GND4") (class "Default")
      (node (ref "U$1") (pin "GND4") (pinfunction "GND4_GND4") (pintype "power_in"))
    )
    (net (code "9") (name "/PWR_POS") (class "Default")
      (node (ref "J1") (pin "8") (pinfunction "8_8") (pintype "passive"))
      (node (ref "J2") (pin "8") (pinfunction "8_8") (pintype "passive"))
      (node (ref "R40") (pin "1") (pinfunction "1_1") (pintype "passive"))
    )
    (net (code "10") (name "/U5V") (class "Default")
      (node (ref "U$1") (pin "U5V") (pinfunction "U5V_U5V") (pintype "power_in"))
    )
    (net (code "11") (name "/VBAT") (class "Default")
      (node (ref "U$1") (pin "VBAT") (pinfunction "VBAT_VBAT") (pintype "power_in"))
    )
    (net (code "12") (name "/VDD") (class "Default")
      (node (ref "U$1") (pin "VDD") (pinfunction "VDD_VDD") (pintype "power_in"))
    )
    (net (code "13") (name "CANRX") (class "Default")
      (node (ref "U$1") (pin "PB8") (pinfunction "PB8_PB8") (pintype "bidirectional"))
      (node (ref "U7") (pin "4") (pinfunction "RXD_4") (pintype "output"))
      (node (ref "U7B") (pin "4") (pinfunction "RXD_4") (pintype "bidirectional"))
    )
    (net (code "14") (name "CANTX") (class "Default")
      (node (ref "U$1") (pin "PB9") (pinfunction "PB9_PB9") (pintype "bidirectional"))
      (node (ref "U7") (pin "1") (pinfunction "TXD_1") (pintype "input"))
      (node (ref "U7B") (pin "1") (pinfunction "TXD_1") (pintype "bidirectional"))
    )
    (net (code "15") (name "E_CS") (class "Default")
      (node (ref "JP9") (pin "4") (pinfunction "4_4") (pintype "passive"))
      (node (ref "R23") (pin "2") (pinfunction "2_2") (pintype "passive"))
      (node (ref "U$1") (pin "PC10") (pinfunction "PC10_PC10") (pintype "bidirectional"))
    )
    (net (code "16") (name "E_LAT") (class "Default")
      (node (ref "JP10") (pin "1") (pinfunction "1_1") (pintype "passive"))
      (node (ref "R22") (pin "2") (pinfunction "2_2") (pintype "passive"))
      (node (ref "U$1") (pin "PC11") (pinfunction "PC11_PC11") (pintype "bidirectional"))
    )
    (net (code "17") (name "GND") (class "Default")
      (node (ref "AP1509") (pin "4") (pinfunction "SD_4") (pintype "bidirectional"))
      (node (ref "AP1509") (pin "5") (pinfunction "GND1_5") (pintype "power_in"))
      (node (ref "AP1509") (pin "6") (pinfunction "GND2_6") (pintype "power_in"))
      (node (ref "AP1509") (pin "7") (pinfunction "GND3_7") (pintype "power_in"))
      (node (ref "AP1509") (pin "8") (pinfunction "GND4_8") (pintype "power_in"))
      (node (ref "C1") (pin "2") (pinfunction "2_2") (pintype "passive"))
      (node (ref "C10") (pin "2") (pinfunction "2_2") (pintype "passive"))
      (node (ref "C11") (pin "2") (pinfunction "2_2") (pintype "passive"))
      (node (ref "C2") (pin "-") (pinfunction "-_-") (pintype "passive"))
      (node (ref "C3") (pin "2") (pinfunction "2_2") (pintype "passive"))
      (node (ref "C4") (pin "2") (pinfunction "2_2") (pintype "passive"))
      (node (ref "C5") (pin "2") (pinfunction "2_2") (pintype "passive"))
      (node (ref "C6") (pin "2") (pinfunction "2_2") (pintype "passive"))
      (node (ref "C7") (pin "2") (pinfunction "2_2") (pintype "passive"))
      (node (ref "C8") (pin "2") (pinfunction "2_2") (pintype "passive"))
      (node (ref "C9") (pin "2") (pinfunction "2_2") (pintype "passive"))
      (node (ref "D1") (pin "A") (pinfunction "A_A") (pintype "passive"))
      (node (ref "IC1") (pin "6") (pinfunction "INH_6") (pintype "input"))
      (node (ref "IC1") (pin "8") (pinfunction "GND_8") (pintype "power_in"))
      (node (ref "IC10") (pin "2") (pinfunction "GNDSIG_2") (pintype "input"))
      (node (ref "IC10") (pin "3") (pinfunction "~{ON/OFF}_3") (pintype "input"))
      (node (ref "IC10") (pin "4") (pinfunction "GND_4") (pintype "power_in"))
      (node (ref "IC3") (pin "13") (pinfunction "G_13") (pintype "input"))
      (node (ref "IC3") (pin "8") (pinfunction "GND_8") (pintype "power_in"))
      (node (ref "IC4") (pin "6") (pinfunction "INH_6") (pintype "input"))
      (node (ref "IC4") (pin "8") (pinfunction "GND_8") (pintype "power_in"))
      (node (ref "IC5") (pin "13") (pinfunction "G_13") (pintype "input"))
      (node (ref "IC5") (pin "8") (pinfunction "GND_8") (pintype "power_in"))
      (node (ref "IC6") (pin "11") (pinfunction "V-_11") (pintype "power_in"))
      (node (ref "IC9") (pin "11") (pinfunction "V-_11") (pintype "power_in"))
      (node (ref "J1") (pin "3") (pinfunction "3_3") (pintype "passive"))
      (node (ref "J1") (pin "6") (pinfunction "6_6") (pintype "passive"))
      (node (ref "J1") (pin "7") (pinfunction "7_7") (pintype "passive"))
      (node (ref "J2") (pin "3") (pinfunction "3_3") (pintype "passive"))
      (node (ref "J2") (pin "6") (pinfunction "6_6") (pintype "passive"))
      (node (ref "J2") (pin "7") (pinfunction "7_7") (pintype "passive"))
      (node (ref "J3") (pin "1") (pinfunction "1_1") (pintype "passive"))
      (node (ref "JP10") (pin "4") (pinfunction "4_4") (pintype "passive"))
      (node (ref "JP11") (pin "5") (pinfunction "5_5") (pintype "passive"))
      (node (ref "JP11") (pin "6") (pinfunction "6_6") (pintype "passive"))
      (node (ref "JP12") (pin "5") (pinfunction "5_5") (pintype "passive"))
      (node (ref "JP12") (pin "6") (pinfunction "6_6") (pintype "passive"))
      (node (ref "JP13") (pin "5") (pinfunction "5_5") (pintype "passive"))
      (node (ref "JP14") (pin "5") (pinfunction "5_5") (pintype "passive"))
      (node (ref "JP15") (pin "5") (pinfunction "5_5") (pintype "passive"))
      (node (ref "JP16") (pin "5") (pinfunction "5_5") (pintype "passive"))
      (node (ref "JP16") (pin "6") (pinfunction "6_6") (pintype "passive"))
      (node (ref "JP7") (pin "5") (pinfunction "5_5") (pintype "passive"))
      (node (ref "JP7") (pin "6") (pinfunction "6_6") (pintype "passive"))
      (node (ref "JP8") (pin "4") (pinfunction "4_4") (pintype "passive"))
      (node (ref "Q1") (pin "2") (pinfunction "S_2") (pintype "passive"))
      (node (ref "Q10") (pin "2") (pinfunction "S_2") (pintype "passive"))
      (node (ref "Q11") (pin "2") (pinfunction "S_2") (pintype "passive"))
      (node (ref "Q12") (pin "2") (pinfunction "S_2") (pintype "passive"))
      (node (ref "Q13") (pin "2") (pinfunction "S_2") (pintype "passive"))
      (node (ref "Q14") (pin "2") (pinfunction "S_2") (pintype "passive"))
      (node (ref "Q15") (pin "2") (pinfunction "S_2") (pintype "passive"))
      (node (ref "Q16") (pin "2") (pinfunction "S_2") (pintype "passive"))
      (node (ref "Q2") (pin "2") (pinfunction "S_2") (pintype "passive"))
      (node (ref "Q3") (pin "2") (pinfunction "S_2") (pintype "passive"))
      (node (ref "Q4") (pin "2") (pinfunction "S_2") (pintype "passive"))
      (node (ref "Q5") (pin "2") (pinfunction "S_2") (pintype "passive"))
      (node (ref "Q6") (pin "2") (pinfunction "S_2") (pintype "passive"))
      (node (ref "Q7") (pin "2") (pinfunction "S_2") (pintype "passive"))
      (node (ref "Q8") (pin "2") (pinfunction "S_2") (pintype "passive"))
      (node (ref "Q9") (pin "2") (pinfunction "S_2") (pintype "passive"))
      (node (ref "R2") (pin "1") (pinfunction "1_1") (pintype "passive"))
      (node (ref "R61") (pin "2") (pinfunction "2_2") (pintype "passive"))
      (node (ref "SJ12") (pin "P$2") (pinfunction "2_P$2") (pintype "passive"))
      (node (ref "SJ3") (pin "2") (pinfunction "2_2") (pintype "passive"))
      (node (ref "SJ6") (pin "P$2") (pinfunction "2_P$2") (pintype "passive"))
      (node (ref "SJ9") (pin "2") (pinfunction "2_2") (pintype "passive"))
      (node (ref "U$1") (pin "GND3") (pinfunction "GND3_GND3") (pintype "power_in"))
      (node (ref "U$1") (pin "GND5") (pinfunction "GND5_GND5") (pintype "power_in"))
      (node (ref "U$1") (pin "GND6") (pinfunction "GND6_GND6") (pintype "power_in"))
      (node (ref "U$1") (pin "GND7") (pinfunction "GND7_GND7") (pintype "power_in"))
      (node (ref "U$1") (pin "GND8") (pinfunction "GND8_GND8") (pintype "power_in"))
      (node (ref "U$2") (pin "3") (pinfunction "VSS_3") (pintype "power_in"))
      (node (ref "U$3") (pin "3") (pinfunction "VSS_3") (pintype "power_in"))
      (node (ref "U$4") (pin "3") (pinfunction "VSS_3") (pintype "power_in"))
      (node (ref "U$5") (pin "3") (pinfunction "VSS_3") (pintype "power_in"))
      (node (ref "U7") (pin "2") (pinfunction "GND_2") (pintype "power_in"))
      (node (ref "U7B") (pin "2") (pinfunction "VSS_2") (pintype "power_in"))
      (node (ref "X1") (pin "2") (pinfunction "2_2") (pintype "passive"))
    )
    (net (code "18") (name "I2CSCL") (class "Default")
      (node (ref "JP8") (pin "2") (pinfunction "2_2") (pintype "passive"))
      (node (ref "R63") (pin "2") (pinfunction "2_2") (pintype "passive"))
      (node (ref "U$1") (pin "PB6") (pinfunction "PB6_PB6") (pintype "bidirectional"))
    )
    (net (code "19") (name "I2CSDA") (class "Default")
      (node (ref "JP8") (pin "1") (pinfunction "1_1") (pintype "passive"))
      (node (ref "R62") (pin "2") (pinfunction "2_2") (pintype "passive"))
      (node (ref "U$1") (pin "PB7") (pinfunction "PB7_PB7") (pintype "bidirectional"))
    )
    (net (code "20") (name "ILAT") (class "Default")
      (node (ref "IC1") (pin "15") (pinfunction "SH/~{LD}_15") (pintype "input"))
      (node (ref "IC4") (pin "15") (pinfunction "SH/~{LD}_15") (pintype "input"))
      (node (ref "U$1") (pin "PA6") (pinfunction "PA6_PA6") (pintype "bidirectional"))
    )
    (net (code "21") (name "MISO") (class "Default")
      (node (ref "JP9") (pin "1") (pinfunction "1_1") (pintype "passive"))
      (node (ref "U$1") (pin "PB4") (pinfunction "PB4_PB4") (pintype "bidirectional"))
    )
    (net (code "22") (name "MISO2") (class "Default")
      (node (ref "IC4") (pin "13") (pinfunction "QH_13") (pintype "output"))
      (node (ref "SJ13") (pin "P$2") (pinfunction "2_P$2") (pintype "passive"))
      (node (ref "U$1") (pin "PC2") (pinfunction "PC2_PC2") (pintype "bidirectional"))
    )
    (net (code "23") (name "MOSI") (class "Default")
      (node (ref "IC5") (pin "14") (pinfunction "SER_14") (pintype "input"))
      (node (ref "R20") (pin "1") (pinfunction "1_1") (pintype "passive"))
      (node (ref "SJ15") (pin "1") (pinfunction "1_1") (pintype "passive"))
      (node (ref "SJ17") (pin "P$2") (pinfunction "2_P$2") (pintype "passive"))
      (node (ref "U$1") (pin "PB5") (pinfunction "PB5_PB5") (pintype "bidirectional"))
    )
    (net (code "24") (name "Net-(AP1509-VOUT)") (class "Default")
      (node (ref "AP1509") (pin "2") (pinfunction "VOUT_2") (pintype "bidirectional"))
      (node (ref "D1") (pin "C") (pinfunction "C_C") (pintype "passive"))
      (node (ref "IC10") (pin "7") (pinfunction "OUT_7") (pintype "passive"))
      (node (ref "L1") (pin "2") (pinfunction "2_2") (pintype "passive"))
    )
    (net (code "25") (name "Net-(D2-PadA)") (class "Default")
      (node (ref "D2") (pin "A") (pinfunction "A_A") (pintype "passive"))
      (node (ref "JP4") (pin "4") (pinfunction "4_4") (pintype "passive"))
    )
    (net (code "26") (name "Net-(D2-PadC)") (class "Default")
      (node (ref "D2") (pin "C") (pinfunction "C_C") (pintype "passive"))
      (node (ref "JP4") (pin "1") (pinfunction "1_1") (pintype "passive"))
    )
    (net (code "27") (name "Net-(IC1A-A)") (class "Default")
      (node (ref "IC1") (pin "2") (pinfunction "A_2") (pintype "input"))
      (node (ref "R36") (pin "1") (pinfunction "1_1") (pintype "passive"))
      (node (ref "RN4") (pin "9") (pinfunction "2_9") (pintype "passive"))
    )
    (net (code "28") (name "Net-(IC1A-B)") (class "Default")
      (node (ref "IC1") (pin "3") (pinfunction "B_3") (pintype "input"))
      (node (ref "R37") (pin "1") (pinfunction "1_1") (pintype "passive"))
      (node (ref "RN4") (pin "10") (pinfunction "2_10") (pintype "passive"))
    )
    (net (code "29") (name "Net-(IC1A-C)") (class "Default")
      (node (ref "IC1") (pin "4") (pinfunction "C_4") (pintype "input"))
      (node (ref "R38") (pin "1") (pinfunction "1_1") (pintype "passive"))
      (node (ref "RN4") (pin "11") (pinfunction "2_11") (pintype "passive"))
    )
    (net (code "30") (name "Net-(IC1A-D)") (class "Default")
      (node (ref "IC1") (pin "5") (pinfunction "D_5") (pintype "input"))
      (node (ref "R39") (pin "1") (pinfunction "1_1") (pintype "passive"))
      (node (ref "RN4") (pin "12") (pinfunction "2_12") (pintype "passive"))
    )
    (net (code "31") (name "Net-(IC1A-E)") (class "Default")
      (node (ref "IC1") (pin "10") (pinfunction "E_10") (pintype "input"))
      (node (ref "R41") (pin "1") (pinfunction "1_1") (pintype "passive"))
      (node (ref "RN4") (pin "13") (pinfunction "2_13") (pintype "passive"))
    )
    (net (code "32") (name "Net-(IC1A-F)") (class "Default")
      (node (ref "IC1") (pin "11") (pinfunction "F_11") (pintype "input"))
      (node (ref "R42") (pin "1") (pinfunction "1_1") (pintype "passive"))
      (node (ref "RN4") (pin "14") (pinfunction "2_14") (pintype "passive"))
    )
    (net (code "33") (name "Net-(IC1A-G)") (class "Default")
      (node (ref "IC1") (pin "12") (pinfunction "G_12") (pintype "input"))
      (node (ref "R43") (pin "1") (pinfunction "1_1") (pintype "passive"))
      (node (ref "RN4") (pin "15") (pinfunction "2_15") (pintype "passive"))
    )
    (net (code "34") (name "Net-(IC1A-H)") (class "Default")
      (node (ref "IC1") (pin "14") (pinfunction "H_14") (pintype "input"))
      (node (ref "R44") (pin "1") (pinfunction "1_1") (pintype "passive"))
      (node (ref "RN4") (pin "16") (pinfunction "2_16") (pintype "passive"))
    )
    (net (code "35") (name "Net-(IC2-CD+)") (class "Default")
      (node (ref "IC2") (pin "10") (pinfunction "CD+_10") (pintype "passive"))
      (node (ref "SJ4") (pin "P$1") (pinfunction "1_P$1") (pintype "passive"))
      (node (ref "SJ5") (pin "P$1") (pinfunction "1_P$1") (pintype "passive"))
      (node (ref "SJ6") (pin "P$1") (pinfunction "1_P$1") (pintype "passive"))
    )
    (net (code "36") (name "Net-(IC2-GND)") (class "Default")
      (node (ref "IC2") (pin "9") (pinfunction "GND_9") (pintype "power_in"))
      (node (ref "SJ1") (pin "P$1") (pinfunction "1_P$1") (pintype "passive"))
      (node (ref "SJ2") (pin "P$1") (pinfunction "1_P$1") (pintype "passive"))
      (node (ref "SJ3") (pin "1") (pinfunction "1_1") (pintype "passive"))
    )
    (net (code "37") (name "Net-(IC2-I1)") (class "Default")
      (node (ref "IC2") (pin "1") (pinfunction "I1_1") (pintype "input"))
      (node (ref "IC5") (pin "15") (pinfunction "QA_15") (pintype "tri_state"))
      (node (ref "R3") (pin "1") (pinfunction "1_1") (pintype "passive"))
    )
    (net (code "38") (name "Net-(IC2-I2)") (class "Default")
      (node (ref "IC2") (pin "2") (pinfunction "I2_2") (pintype "input"))
      (node (ref "IC5") (pin "1") (pinfunction "QB_1") (pintype "tri_state"))
      (node (ref "R4") (pin "1") (pinfunction "1_1") (pintype "passive"))
    )
    (net (code "39") (name "Net-(IC2-I3)") (class "Default")
      (node (ref "IC2") (pin "3") (pinfunction "I3_3") (pintype "input"))
      (node (ref "IC5") (pin "2") (pinfunction "QC_2") (pintype "tri_state"))
      (node (ref "R5") (pin "1") (pinfunction "1_1") (pintype "passive"))
    )
    (net (code "40") (name "Net-(IC2-I4)") (class "Default")
      (node (ref "IC2") (pin "4") (pinfunction "I4_4") (pintype "input"))
      (node (ref "IC5") (pin "3") (pinfunction "QD_3") (pintype "tri_state"))
      (node (ref "R6") (pin "1") (pinfunction "1_1") (pintype "passive"))
    )
    (net (code "41") (name "Net-(IC2-I5)") (class "Default")
      (node (ref "IC2") (pin "5") (pinfunction "I5_5") (pintype "input"))
      (node (ref "IC5") (pin "4") (pinfunction "QE_4") (pintype "tri_state"))
      (node (ref "R7") (pin "1") (pinfunction "1_1") (pintype "passive"))
    )
    (net (code "42") (name "Net-(IC2-I6)") (class "Default")
      (node (ref "IC2") (pin "6") (pinfunction "I6_6") (pintype "input"))
      (node (ref "IC5") (pin "5") (pinfunction "QF_5") (pintype "tri_state"))
      (node (ref "R8") (pin "1") (pinfunction "1_1") (pintype "passive"))
    )
    (net (code "43") (name "Net-(IC2-I7)") (class "Default")
      (node (ref "IC2") (pin "7") (pinfunction "I7_7") (pintype "input"))
      (node (ref "IC5") (pin "6") (pinfunction "QG_6") (pintype "tri_state"))
      (node (ref "R9") (pin "1") (pinfunction "1_1") (pintype "passive"))
    )
    (net (code "44") (name "Net-(IC2-I8)") (class "Default")
      (node (ref "IC2") (pin "8") (pinfunction "I8_8") (pintype "input"))
      (node (ref "IC5") (pin "7") (pinfunction "QH_7") (pintype "tri_state"))
      (node (ref "R10") (pin "1") (pinfunction "1_1") (pintype "passive"))
    )
    (net (code "45") (name "Net-(IC2-O1)") (class "Default")
      (node (ref "IC2") (pin "18") (pinfunction "O1_18") (pintype "open_collector"))
      (node (ref "JP1") (pin "1") (pinfunction "1_1") (pintype "passive"))
      (node (ref "Q1") (pin "3") (pinfunction "D_3") (pintype "passive"))
    )
    (net (code "46") (name "Net-(IC2-O2)") (class "Default")
      (node (ref "IC2") (pin "17") (pinfunction "O2_17") (pintype "open_collector"))
      (node (ref "JP1") (pin "2") (pinfunction "2_2") (pintype "passive"))
      (node (ref "Q2") (pin "3") (pinfunction "D_3") (pintype "passive"))
    )
    (net (code "47") (name "Net-(IC2-O3)") (class "Default")
      (node (ref "IC2") (pin "16") (pinfunction "O3_16") (pintype "open_collector"))
      (node (ref "JP1") (pin "3") (pinfunction "3_3") (pintype "passive"))
      (node (ref "Q3") (pin "3") (pinfunction "D_3") (pintype "passive"))
    )
    (net (code "48") (name "Net-(IC2-O4)") (class "Default")
      (node (ref "IC2") (pin "15") (pinfunction "O4_15") (pintype "open_collector"))
      (node (ref "JP1") (pin "4") (pinfunction "4_4") (pintype "passive"))
      (node (ref "Q4") (pin "3") (pinfunction "D_3") (pintype "passive"))
    )
    (net (code "49") (name "Net-(IC2-O5)") (class "Default")
      (node (ref "IC2") (pin "14") (pinfunction "O5_14") (pintype "open_collector"))
      (node (ref "JP1") (pin "5") (pinfunction "5_5") (pintype "passive"))
      (node (ref "Q5") (pin "3") (pinfunction "D_3") (pintype "passive"))
    )
    (net (code "50") (name "Net-(IC2-O6)") (class "Default")
      (node (ref "IC2") (pin "13") (pinfunction "O6_13") (pintype "open_collector"))
      (node (ref "JP1") (pin "6") (pinfunction "6_6") (pintype "passive"))
      (node (ref "Q6") (pin "3") (pinfunction "D_3") (pintype "passive"))
    )
    (net (code "51") (name "Net-(IC2-O7)") (class "Default")
      (node (ref "IC2") (pin "12") (pinfunction "O7_12") (pintype "open_collector"))
      (node (ref "JP1") (pin "7") (pinfunction "7_7") (pintype "passive"))
      (node (ref "Q7") (pin "3") (pinfunction "D_3") (pintype "passive"))
    )
    (net (code "52") (name "Net-(IC2-O8)") (class "Default")
      (node (ref "IC2") (pin "11") (pinfunction "O8_11") (pintype "open_collector"))
      (node (ref "JP1") (pin "8") (pinfunction "8_8") (pintype "passive"))
      (node (ref "Q8") (pin "3") (pinfunction "D_3") (pintype "passive"))
    )
    (net (code "53") (name "Net-(IC3A-QA)") (class "Default")
      (node (ref "IC3") (pin "15") (pinfunction "QA_15") (pintype "tri_state"))
      (node (ref "IC8") (pin "1") (pinfunction "I1_1") (pintype "input"))
      (node (ref "R11") (pin "1") (pinfunction "1_1") (pintype "passive"))
    )
    (net (code "54") (name "Net-(IC3A-QB)") (class "Default")
      (node (ref "IC3") (pin "1") (pinfunction "QB_1") (pintype "tri_state"))
      (node (ref "IC8") (pin "2") (pinfunction "I2_2") (pintype "input"))
      (node (ref "R12") (pin "1") (pinfunction "1_1") (pintype "passive"))
    )
    (net (code "55") (name "Net-(IC3A-QC)") (class "Default")
      (node (ref "IC3") (pin "2") (pinfunction "QC_2") (pintype "tri_state"))
      (node (ref "IC8") (pin "3") (pinfunction "I3_3") (pintype "input"))
      (node (ref "R13") (pin "1") (pinfunction "1_1") (pintype "passive"))
    )
    (net (code "56") (name "Net-(IC3A-QD)") (class "Default")
      (node (ref "IC3") (pin "3") (pinfunction "QD_3") (pintype "tri_state"))
      (node (ref "IC8") (pin "4") (pinfunction "I4_4") (pintype "input"))
      (node (ref "R14") (pin "1") (pinfunction "1_1") (pintype "passive"))
    )
    (net (code "57") (name "Net-(IC3A-QE)") (class "Default")
      (node (ref "IC3") (pin "4") (pinfunction "QE_4") (pintype "tri_state"))
      (node (ref "IC8") (pin "5") (pinfunction "I5_5") (pintype "input"))
      (node (ref "R15") (pin "1") (pinfunction "1_1") (pintype "passive"))
    )
    (net (code "58") (name "Net-(IC3A-QF)") (class "Default")
      (node (ref "IC3") (pin "5") (pinfunction "QF_5") (pintype "tri_state"))
      (node (ref "IC8") (pin "6") (pinfunction "I6_6") (pintype "input"))
      (node (ref "R16") (pin "1") (pinfunction "1_1") (pintype "passive"))
    )
    (net (code "59") (name "Net-(IC3A-QG)") (class "Default")
      (node (ref "IC3") (pin "6") (pinfunction "QG_6") (pintype "tri_state"))
      (node (ref "IC8") (pin "7") (pinfunction "I7_7") (pintype "input"))
      (node (ref "R17") (pin "1") (pinfunction "1_1") (pintype "passive"))
    )
    (net (code "60") (name "Net-(IC3A-QH)") (class "Default")
      (node (ref "IC3") (pin "7") (pinfunction "QH_7") (pintype "tri_state"))
      (node (ref "IC8") (pin "8") (pinfunction "I8_8") (pintype "input"))
      (node (ref "R18") (pin "1") (pinfunction "1_1") (pintype "passive"))
    )
    (net (code "61") (name "Net-(IC4A-A)") (class "Default")
      (node (ref "IC4") (pin "2") (pinfunction "A_2") (pintype "input"))
      (node (ref "R28") (pin "1") (pinfunction "1_1") (pintype "passive"))
      (node (ref "RN1") (pin "9") (pinfunction "2_9") (pintype "passive"))
    )
    (net (code "62") (name "Net-(IC4A-B)") (class "Default")
      (node (ref "IC4") (pin "3") (pinfunction "B_3") (pintype "input"))
      (node (ref "R29") (pin "1") (pinfunction "1_1") (pintype "passive"))
      (node (ref "RN1") (pin "10") (pinfunction "2_10") (pintype "passive"))
    )
    (net (code "63") (name "Net-(IC4A-C)") (class "Default")
      (node (ref "IC4") (pin "4") (pinfunction "C_4") (pintype "input"))
      (node (ref "R30") (pin "1") (pinfunction "1_1") (pintype "passive"))
      (node (ref "RN1") (pin "11") (pinfunction "2_11") (pintype "passive"))
    )
    (net (code "64") (name "Net-(IC4A-D)") (class "Default")
      (node (ref "IC4") (pin "5") (pinfunction "D_5") (pintype "input"))
      (node (ref "R31") (pin "1") (pinfunction "1_1") (pintype "passive"))
      (node (ref "RN1") (pin "12") (pinfunction "2_12") (pintype "passive"))
    )
    (net (code "65") (name "Net-(IC4A-E)") (class "Default")
      (node (ref "IC4") (pin "10") (pinfunction "E_10") (pintype "input"))
      (node (ref "R32") (pin "1") (pinfunction "1_1") (pintype "passive"))
      (node (ref "RN1") (pin "13") (pinfunction "2_13") (pintype "passive"))
    )
    (net (code "66") (name "Net-(IC4A-F)") (class "Default")
      (node (ref "IC4") (pin "11") (pinfunction "F_11") (pintype "input"))
      (node (ref "R33") (pin "1") (pinfunction "1_1") (pintype "passive"))
      (node (ref "RN1") (pin "14") (pinfunction "2_14") (pintype "passive"))
    )
    (net (code "67") (name "Net-(IC4A-G)") (class "Default")
      (node (ref "IC4") (pin "12") (pinfunction "G_12") (pintype "input"))
      (node (ref "R34") (pin "1") (pinfunction "1_1") (pintype "passive"))
      (node (ref "RN1") (pin "15") (pinfunction "2_15") (pintype "passive"))
    )
    (net (code "68") (name "Net-(IC4A-H)") (class "Default")
      (node (ref "IC4") (pin "14") (pinfunction "H_14") (pintype "input"))
      (node (ref "R35") (pin "1") (pinfunction "1_1") (pintype "passive"))
      (node (ref "RN1") (pin "16") (pinfunction "2_16") (pintype "passive"))
    )
    (net (code "69") (name "Net-(IC6A--IN)") (class "Default")
      (node (ref "IC6") (pin "13") (pinfunction "-IN_13") (pintype "input"))
      (node (ref "IC6") (pin "2") (pinfunction "-IN_2") (pintype "input"))
      (node (ref "IC6") (pin "6") (pinfunction "-IN_6") (pintype "input"))
      (node (ref "IC6") (pin "9") (pinfunction "-IN_9") (pintype "input"))
      (node (ref "IC9") (pin "13") (pinfunction "-IN_13") (pintype "input"))
      (node (ref "IC9") (pin "2") (pinfunction "-IN_2") (pintype "input"))
      (node (ref "IC9") (pin "6") (pinfunction "-IN_6") (pintype "input"))
      (node (ref "IC9") (pin "9") (pinfunction "-IN_9") (pintype "input"))
      (node (ref "R1") (pin "1") (pinfunction "1_1") (pintype "passive"))
      (node (ref "R2") (pin "2") (pinfunction "2_2") (pintype "passive"))
    )
    (net (code "70") (name "Net-(IC6A-OUT)") (class "Default")
      (node (ref "IC6") (pin "1") (pinfunction "OUT_1") (pintype "output"))
      (node (ref "JP15") (pin "3") (pinfunction "3_3") (pintype "passive"))
      (node (ref "JP5") (pin "3") (pinfunction "3_3") (pintype "passive"))
      (node (ref "U$5") (pin "5") (pinfunction "O_5") (pintype "output"))
    )
    (net (code "71") (name "Net-(IC6B-OUT)") (class "Default")
      (node (ref "IC6") (pin "7") (pinfunction "OUT_7") (pintype "output"))
      (node (ref "JP15") (pin "1") (pinfunction "1_1") (pintype "passive"))
      (node (ref "JP5") (pin "1") (pinfunction "1_1") (pintype "passive"))
      (node (ref "U$4") (pin "7") (pinfunction "O_7") (pintype "output"))
    )
    (net (code "72") (name "Net-(IC6C-OUT)") (class "Default")
      (node (ref "IC6") (pin "8") (pinfunction "OUT_8") (pintype "output"))
      (node (ref "JP15") (pin "2") (pinfunction "2_2") (pintype "passive"))
      (node (ref "JP5") (pin "2") (pinfunction "2_2") (pintype "passive"))
      (node (ref "U$4") (pin "5") (pinfunction "O_5") (pintype "output"))
    )
    (net (code "73") (name "Net-(IC6D-OUT)") (class "Default")
      (node (ref "IC6") (pin "14") (pinfunction "OUT_14") (pintype "output"))
      (node (ref "JP15") (pin "4") (pinfunction "4_4") (pintype "passive"))
      (node (ref "JP5") (pin "4") (pinfunction "4_4") (pintype "passive"))
      (node (ref "U$5") (pin "7") (pinfunction "O_7") (pintype "output"))
    )
    (net (code "74") (name "Net-(IC8-CD+)") (class "Default")
      (node (ref "IC8") (pin "10") (pinfunction "CD+_10") (pintype "passive"))
      (node (ref "SJ10") (pin "P$1") (pinfunction "1_P$1") (pintype "passive"))
      (node (ref "SJ11") (pin "P$1") (pinfunction "1_P$1") (pintype "passive"))
      (node (ref "SJ12") (pin "P$1") (pinfunction "1_P$1") (pintype "passive"))
    )
    (net (code "75") (name "Net-(IC8-GND)") (class "Default")
      (node (ref "IC8") (pin "9") (pinfunction "GND_9") (pintype "power_in"))
      (node (ref "SJ7") (pin "P$1") (pinfunction "1_P$1") (pintype "passive"))
      (node (ref "SJ8") (pin "P$1") (pinfunction "1_P$1") (pintype "passive"))
      (node (ref "SJ9") (pin "1") (pinfunction "1_1") (pintype "passive"))
    )
    (net (code "76") (name "Net-(IC8-O1)") (class "Default")
      (node (ref "IC8") (pin "18") (pinfunction "O1_18") (pintype "open_collector"))
      (node (ref "JP6") (pin "1") (pinfunction "1_1") (pintype "passive"))
      (node (ref "Q9") (pin "3") (pinfunction "D_3") (pintype "passive"))
    )
    (net (code "77") (name "Net-(IC8-O2)") (class "Default")
      (node (ref "IC8") (pin "17") (pinfunction "O2_17") (pintype "open_collector"))
      (node (ref "JP6") (pin "2") (pinfunction "2_2") (pintype "passive"))
      (node (ref "Q10") (pin "3") (pinfunction "D_3") (pintype "passive"))
    )
    (net (code "78") (name "Net-(IC8-O3)") (class "Default")
      (node (ref "IC8") (pin "16") (pinfunction "O3_16") (pintype "open_collector"))
      (node (ref "JP6") (pin "3") (pinfunction "3_3") (pintype "passive"))
      (node (ref "Q11") (pin "3") (pinfunction "D_3") (pintype "passive"))
    )
    (net (code "79") (name "Net-(IC8-O4)") (class "Default")
      (node (ref "IC8") (pin "15") (pinfunction "O4_15") (pintype "open_collector"))
      (node (ref "JP6") (pin "4") (pinfunction "4_4") (pintype "passive"))
      (node (ref "Q12") (pin "3") (pinfunction "D_3") (pintype "passive"))
    )
    (net (code "80") (name "Net-(IC8-O5)") (class "Default")
      (node (ref "IC8") (pin "14") (pinfunction "O5_14") (pintype "open_collector"))
      (node (ref "JP6") (pin "5") (pinfunction "5_5") (pintype "passive"))
      (node (ref "Q13") (pin "3") (pinfunction "D_3") (pintype "passive"))
    )
    (net (code "81") (name "Net-(IC8-O6)") (class "Default")
      (node (ref "IC8") (pin "13") (pinfunction "O6_13") (pintype "open_collector"))
      (node (ref "JP6") (pin "6") (pinfunction "6_6") (pintype "passive"))
      (node (ref "Q14") (pin "3") (pinfunction "D_3") (pintype "passive"))
    )
    (net (code "82") (name "Net-(IC8-O7)") (class "Default")
      (node (ref "IC8") (pin "12") (pinfunction "O7_12") (pintype "open_collector"))
      (node (ref "JP6") (pin "7") (pinfunction "7_7") (pintype "passive"))
      (node (ref "Q15") (pin "3") (pinfunction "D_3") (pintype "passive"))
    )
    (net (code "83") (name "Net-(IC8-O8)") (class "Default")
      (node (ref "IC8") (pin "11") (pinfunction "O8_11") (pintype "open_collector"))
      (node (ref "JP6") (pin "8") (pinfunction "8_8") (pintype "passive"))
      (node (ref "Q16") (pin "3") (pinfunction "D_3") (pintype "passive"))
    )
    (net (code "84") (name "Net-(IC9A-OUT)") (class "Default")
      (node (ref "IC9") (pin "1") (pinfunction "OUT_1") (pintype "output"))
      (node (ref "JP15") (pin "9") (pinfunction "9_9") (pintype "passive"))
      (node (ref "JP5") (pin "7") (pinfunction "7_7") (pintype "passive"))
      (node (ref "U$3") (pin "5") (pinfunction "O_5") (pintype "output"))
    )
    (net (code "85") (name "Net-(IC9B-OUT)") (class "Default")
      (node (ref "IC9") (pin "7") (pinfunction "OUT_7") (pintype "output"))
      (node (ref "JP15") (pin "7") (pinfunction "7_7") (pintype "passive"))
      (node (ref "JP5") (pin "5") (pinfunction "5_5") (pintype "passive"))
      (node (ref "U$2") (pin "7") (pinfunction "O_7") (pintype "output"))
    )
    (net (code "86") (name "Net-(IC9C-OUT)") (class "Default")
      (node (ref "IC9") (pin "8") (pinfunction "OUT_8") (pintype "output"))
      (node (ref "JP15") (pin "8") (pinfunction "8_8") (pintype "passive"))
      (node (ref "JP5") (pin "6") (pinfunction "6_6") (pintype "passive"))
      (node (ref "U$2") (pin "5") (pinfunction "O_5") (pintype "output"))
    )
    (net (code "87") (name "Net-(IC9D-OUT)") (class "Default")
      (node (ref "IC9") (pin "14") (pinfunction "OUT_14") (pintype "output"))
      (node (ref "JP15") (pin "10") (pinfunction "10_10") (pintype "passive"))
      (node (ref "JP5") (pin "8") (pinfunction "8_8") (pintype "passive"))
      (node (ref "U$3") (pin "7") (pinfunction "O_7") (pintype "output"))
    )
    (net (code "88") (name "Net-(J1-Pad4)") (class "Default")
      (node (ref "J1") (pin "4") (pinfunction "4_4") (pintype "passive"))
      (node (ref "J2") (pin "4") (pinfunction "4_4") (pintype "passive"))
    )
    (net (code "89") (name "Net-(J1-Pad5)") (class "Default")
      (node (ref "J1") (pin "5") (pinfunction "5_5") (pintype "passive"))
      (node (ref "J2") (pin "5") (pinfunction "5_5") (pintype "passive"))
    )
    (net (code "90") (name "Net-(JP4-Pad3)") (class "Default")
      (node (ref "JP4") (pin "3") (pinfunction "3_3") (pintype "passive"))
      (node (ref "R40") (pin "2") (pinfunction "2_2") (pintype "passive"))
    )
    (net (code "91") (name "Net-(JP13-Pad1)") (class "Default")
      (node (ref "JP13") (pin "1") (pinfunction "1_1") (pintype "passive"))
      (node (ref "JP3") (pin "1") (pinfunction "1_1") (pintype "passive"))
      (node (ref "R44") (pin "2") (pinfunction "2_2") (pintype "passive"))
      (node (ref "R53") (pin "2") (pinfunction "2_2") (pintype "passive"))
      (node (ref "RN4") (pin "1") (pinfunction "1_1") (pintype "passive"))
      (node (ref "RN5") (pin "9") (pinfunction "9_9") (pintype "passive"))
    )
    (net (code "92") (name "Net-(JP14-Pad1)") (class "Default")
      (node (ref "JP14") (pin "1") (pinfunction "1_1") (pintype "passive"))
      (node (ref "JP2") (pin "1") (pinfunction "1_1") (pintype "passive"))
      (node (ref "R35") (pin "2") (pinfunction "2_2") (pintype "passive"))
      (node (ref "R45") (pin "2") (pinfunction "2_2") (pintype "passive"))
      (node (ref "RN1") (pin "1") (pinfunction "1_1") (pintype "passive"))
      (node (ref "RN2") (pin "9") (pinfunction "9_9") (pintype "passive"))
    )
    (net (code "93") (name "Net-(Q1-G)") (class "Default")
      (node (ref "Q1") (pin "1") (pinfunction "G_1") (pintype "passive"))
      (node (ref "R3") (pin "2") (pinfunction "2_2") (pintype "passive"))
    )
    (net (code "94") (name "Net-(Q2-G)") (class "Default")
      (node (ref "Q2") (pin "1") (pinfunction "G_1") (pintype "passive"))
      (node (ref "R4") (pin "2") (pinfunction "2_2") (pintype "passive"))
    )
    (net (code "95") (name "Net-(Q3-G)") (class "Default")
      (node (ref "Q3") (pin "1") (pinfunction "G_1") (pintype "passive"))
      (node (ref "R5") (pin "2") (pinfunction "2_2") (pintype "passive"))
    )
    (net (code "96") (name "Net-(Q4-G)") (class "Default")
      (node (ref "Q4") (pin "1") (pinfunction "G_1") (pintype "passive"))
      (node (ref "R6") (pin "2") (pinfunction "2_2") (pintype "passive"))
    )
    (net (code "97") (name "Net-(Q5-G)") (class "Default")
      (node (ref "Q5") (pin "1") (pinfunction "G_1") (pintype "passive"))
      (node (ref "R7") (pin "2") (pinfunction "2_2") (pintype "passive"))
    )
    (net (code "98") (name "Net-(Q6-G)") (class "Default")
      (node (ref "Q6") (pin "1") (pinfunction "G_1") (pintype "passive"))
      (node (ref "R8") (pin "2") (pinfunction "2_2") (pintype "passive"))
    )
    (net (code "99") (name "Net-(Q7-G)") (class "Default")
      (node (ref "Q7") (pin "1") (pinfunction "G_1") (pintype "passive"))
      (node (ref "R9") (pin "2") (pinfunction "2_2") (pintype "passive"))
    )
    (net (code "100") (name "Net-(Q8-G)") (class "Default")
      (node (ref "Q8") (pin "1") (pinfunction "G_1") (pintype "passive"))
      (node (ref "R10") (pin "2") (pinfunction "2_2") (pintype "passive"))
    )
    (net (code "101") (name "Net-(Q9-G)") (class "Default")
      (node (ref "Q9") (pin "1") (pinfunction "G_1") (pintype "passive"))
      (node (ref "R11") (pin "2") (pinfunction "2_2") (pintype "passive"))
    )
    (net (code "102") (name "Net-(Q10-G)") (class "Default")
      (node (ref "Q10") (pin "1") (pinfunction "G_1") (pintype "passive"))
      (node (ref "R12") (pin "2") (pinfunction "2_2") (pintype "passive"))
    )
    (net (code "103") (name "Net-(Q11-G)") (class "Default")
      (node (ref "Q11") (pin "1") (pinfunction "G_1") (pintype "passive"))
      (node (ref "R13") (pin "2") (pinfunction "2_2") (pintype "passive"))
    )
    (net (code "104") (name "Net-(Q12-G)") (class "Default")
      (node (ref "Q12") (pin "1") (pinfunction "G_1") (pintype "passive"))
      (node (ref "R14") (pin "2") (pinfunction "2_2") (pintype "passive"))
    )
    (net (code "105") (name "Net-(Q13-G)") (class "Default")
      (node (ref "Q13") (pin "1") (pinfunction "G_1") (pintype "passive"))
      (node (ref "R15") (pin "2") (pinfunction "2_2") (pintype "passive"))
    )
    (net (code "106") (name "Net-(Q14-G)") (class "Default")
      (node (ref "Q14") (pin "1") (pinfunction "G_1") (pintype "passive"))
      (node (ref "R16") (pin "2") (pinfunction "2_2") (pintype "passive"))
    )
    (net (code "107") (name "Net-(Q15-G)") (class "Default")
      (node (ref "Q15") (pin "1") (pinfunction "G_1") (pintype "passive"))
      (node (ref "R17") (pin "2") (pinfunction "2_2") (pintype "passive"))
    )
    (net (code "108") (name "Net-(Q16-G)") (class "Default")
      (node (ref "Q16") (pin "1") (pinfunction "G_1") (pintype "passive"))
      (node (ref "R18") (pin "2") (pinfunction "2_2") (pintype "passive"))
    )
    (net (code "109") (name "Net-(RN1B-1)") (class "Default")
      (node (ref "JP14") (pin "2") (pinfunction "2_2") (pintype "passive"))
      (node (ref "JP2") (pin "2") (pinfunction "2_2") (pintype "passive"))
      (node (ref "R34") (pin "2") (pinfunction "2_2") (pintype "passive"))
      (node (ref "R46") (pin "1") (pinfunction "1_1") (pintype "passive"))
      (node (ref "RN1") (pin "2") (pinfunction "1_2") (pintype "passive"))
      (node (ref "RN2") (pin "8") (pinfunction "8_8") (pintype "passive"))
    )
    (net (code "110") (name "Net-(RN1C-1)") (class "Default")
      (node (ref "JP14") (pin "3") (pinfunction "3_3") (pintype "passive"))
      (node (ref "JP2") (pin "3") (pinfunction "3_3") (pintype "passive"))
      (node (ref "R33") (pin "2") (pinfunction "2_2") (pintype "passive"))
      (node (ref "R47") (pin "1") (pinfunction "1_1") (pintype "passive"))
      (node (ref "RN1") (pin "3") (pinfunction "1_3") (pintype "passive"))
      (node (ref "RN2") (pin "7") (pinfunction "7_7") (pintype "passive"))
    )
    (net (code "111") (name "Net-(RN1D-1)") (class "Default")
      (node (ref "JP14") (pin "4") (pinfunction "4_4") (pintype "passive"))
      (node (ref "JP2") (pin "4") (pinfunction "4_4") (pintype "passive"))
      (node (ref "R32") (pin "2") (pinfunction "2_2") (pintype "passive"))
      (node (ref "R48") (pin "1") (pinfunction "1_1") (pintype "passive"))
      (node (ref "RN1") (pin "4") (pinfunction "1_4") (pintype "passive"))
      (node (ref "RN2") (pin "6") (pinfunction "6_6") (pintype "passive"))
    )
    (net (code "112") (name "Net-(RN1E-1)") (class "Default")
      (node (ref "JP14") (pin "7") (pinfunction "7_7") (pintype "passive"))
      (node (ref "JP2") (pin "5") (pinfunction "5_5") (pintype "passive"))
      (node (ref "R31") (pin "2") (pinfunction "2_2") (pintype "passive"))
      (node (ref "R49") (pin "1") (pinfunction "1_1") (pintype "passive"))
      (node (ref "RN1") (pin "5") (pinfunction "1_5") (pintype "passive"))
      (node (ref "RN2") (pin "5") (pinfunction "5_5") (pintype "passive"))
    )
    (net (code "113") (name "Net-(RN1F-1)") (class "Default")
      (node (ref "JP14") (pin "8") (pinfunction "8_8") (pintype "passive"))
      (node (ref "JP2") (pin "6") (pinfunction "6_6") (pintype "passive"))
      (node (ref "R30") (pin "2") (pinfunction "2_2") (pintype "passive"))
      (node (ref "R50") (pin "1") (pinfunction "1_1") (pintype "passive"))
      (node (ref "RN1") (pin "6") (pinfunction "1_6") (pintype "passive"))
      (node (ref "RN2") (pin "4") (pinfunction "4_4") (pintype "passive"))
    )
    (net (code "114") (name "Net-(RN1G-1)") (class "Default")
      (node (ref "JP14") (pin "9") (pinfunction "9_9") (pintype "passive"))
      (node (ref "JP2") (pin "7") (pinfunction "7_7") (pintype "passive"))
      (node (ref "R29") (pin "2") (pinfunction "2_2") (pintype "passive"))
      (node (ref "R51") (pin "1") (pinfunction "1_1") (pintype "passive"))
      (node (ref "RN1") (pin "7") (pinfunction "1_7") (pintype "passive"))
      (node (ref "RN2") (pin "3") (pinfunction "3_3") (pintype "passive"))
    )
    (net (code "115") (name "Net-(RN1H-1)") (class "Default")
      (node (ref "JP14") (pin "10") (pinfunction "10_10") (pintype "passive"))
      (node (ref "JP2") (pin "8") (pinfunction "8_8") (pintype "passive"))
      (node (ref "R28") (pin "2") (pinfunction "2_2") (pintype "passive"))
      (node (ref "R52") (pin "1") (pinfunction "1_1") (pintype "passive"))
      (node (ref "RN1") (pin "8") (pinfunction "1_8") (pintype "passive"))
      (node (ref "RN2") (pin "2") (pinfunction "2_2") (pintype "passive"))
    )
    (net (code "116") (name "Net-(RN4B-1)") (class "Default")
      (node (ref "JP13") (pin "2") (pinfunction "2_2") (pintype "passive"))
      (node (ref "JP3") (pin "2") (pinfunction "2_2") (pintype "passive"))
      (node (ref "R43") (pin "2") (pinfunction "2_2") (pintype "passive"))
      (node (ref "R54") (pin "2") (pinfunction "2_2") (pintype "passive"))
      (node (ref "RN4") (pin "2") (pinfunction "1_2") (pintype "passive"))
      (node (ref "RN5") (pin "8") (pinfunction "8_8") (pintype "passive"))
    )
    (net (code "117") (name "Net-(RN4C-1)") (class "Default")
      (node (ref "JP13") (pin "3") (pinfunction "3_3") (pintype "passive"))
      (node (ref "JP3") (pin "3") (pinfunction "3_3") (pintype "passive"))
      (node (ref "R42") (pin "2") (pinfunction "2_2") (pintype "passive"))
      (node (ref "R55") (pin "2") (pinfunction "2_2") (pintype "passive"))
      (node (ref "RN4") (pin "3") (pinfunction "1_3") (pintype "passive"))
      (node (ref "RN5") (pin "7") (pinfunction "7_7") (pintype "passive"))
    )
    (net (code "118") (name "Net-(RN4D-1)") (class "Default")
      (node (ref "JP13") (pin "4") (pinfunction "4_4") (pintype "passive"))
      (node (ref "JP3") (pin "4") (pinfunction "4_4") (pintype "passive"))
      (node (ref "R41") (pin "2") (pinfunction "2_2") (pintype "passive"))
      (node (ref "R56") (pin "2") (pinfunction "2_2") (pintype "passive"))
      (node (ref "RN4") (pin "4") (pinfunction "1_4") (pintype "passive"))
      (node (ref "RN5") (pin "6") (pinfunction "6_6") (pintype "passive"))
    )
    (net (code "119") (name "Net-(RN4E-1)") (class "Default")
      (node (ref "JP13") (pin "7") (pinfunction "7_7") (pintype "passive"))
      (node (ref "JP3") (pin "5") (pinfunction "5_5") (pintype "passive"))
      (node (ref "R39") (pin "2") (pinfunction "2_2") (pintype "passive"))
      (node (ref "R57") (pin "2") (pinfunction "2_2") (pintype "passive"))
      (node (ref "RN4") (pin "5") (pinfunction "1_5") (pintype "passive"))
      (node (ref "RN5") (pin "5") (pinfunction "5_5") (pintype "passive"))
    )
    (net (code "120") (name "Net-(RN4F-1)") (class "Default")
      (node (ref "JP13") (pin "8") (pinfunction "8_8") (pintype "passive"))
      (node (ref "JP3") (pin "6") (pinfunction "6_6") (pintype "passive"))
      (node (ref "R38") (pin "2") (pinfunction "2_2") (pintype "passive"))
      (node (ref "R58") (pin "2") (pinfunction "2_2") (pintype "passive"))
      (node (ref "RN4") (pin "6") (pinfunction "1_6") (pintype "passive"))
      (node (ref "RN5") (pin "4") (pinfunction "4_4") (pintype "passive"))
    )
    (net (code "121") (name "Net-(RN4G-1)") (class "Default")
      (node (ref "JP13") (pin "9") (pinfunction "9_9") (pintype "passive"))
      (node (ref "JP3") (pin "7") (pinfunction "7_7") (pintype "passive"))
      (node (ref "R37") (pin "2") (pinfunction "2_2") (pintype "passive"))
      (node (ref "R59") (pin "2") (pinfunction "2_2") (pintype "passive"))
      (node (ref "RN4") (pin "7") (pinfunction "1_7") (pintype "passive"))
      (node (ref "RN5") (pin "3") (pinfunction "3_3") (pintype "passive"))
    )
    (net (code "122") (name "Net-(RN4H-1)") (class "Default")
      (node (ref "JP13") (pin "10") (pinfunction "10_10") (pintype "passive"))
      (node (ref "JP3") (pin "8") (pinfunction "8_8") (pintype "passive"))
      (node (ref "R36") (pin "2") (pinfunction "2_2") (pintype "passive"))
      (node (ref "R60") (pin "2") (pinfunction "2_2") (pintype "passive"))
      (node (ref "RN4") (pin "8") (pinfunction "1_8") (pintype "passive"))
      (node (ref "RN5") (pin "2") (pinfunction "2_2") (pintype "passive"))
    )
    (net (code "123") (name "Net-(SJ13-1)") (class "Default")
      (node (ref "SJ13") (pin "P$1") (pinfunction "1_P$1") (pintype "passive"))
      (node (ref "U$1") (pin "PB14") (pinfunction "PB14_PB14") (pintype "bidirectional"))
    )
    (net (code "124") (name "Net-(SJ14-1)") (class "Default")
      (node (ref "SJ14") (pin "P$1") (pinfunction "1_P$1") (pintype "passive"))
      (node (ref "U$1") (pin "VIN2") (pinfunction "VIN2_VIN2") (pintype "power_in"))
    )
    (net (code "125") (name "Net-(SJ16-2)") (class "Default")
      (node (ref "JP9") (pin "2") (pinfunction "2_2") (pintype "passive"))
      (node (ref "SJ15") (pin "2") (pinfunction "2_2") (pintype "passive"))
      (node (ref "SJ16") (pin "P$2") (pinfunction "2_P$2") (pintype "passive"))
    )
    (net (code "126") (name "Net-(SJ18-2)") (class "Default")
      (node (ref "SJ18") (pin "P$2") (pinfunction "2_P$2") (pintype "passive"))
      (node (ref "U7") (pin "5") (pinfunction "VREF_5") (pintype "output"))
      (node (ref "U7B") (pin "5") (pinfunction "VREF_5") (pintype "bidirectional"))
    )
    (net (code "127") (name "Net-(U7-RS)") (class "Default")
      (node (ref "R61") (pin "1") (pinfunction "1_1") (pintype "passive"))
      (node (ref "U7") (pin "8") (pinfunction "RS_8") (pintype "input"))
      (node (ref "U7B") (pin "8") (pinfunction "RS_8") (pintype "bidirectional"))
    )
    (net (code "128") (name "OLAT") (class "Default")
      (node (ref "IC3") (pin "12") (pinfunction "RCK_12") (pintype "input"))
      (node (ref "IC5") (pin "12") (pinfunction "RCK_12") (pintype "input"))
      (node (ref "R21") (pin "1") (pinfunction "1_1") (pintype "passive"))
      (node (ref "U$1") (pin "PA8") (pinfunction "PA8_PA8") (pintype "bidirectional"))
    )
    (net (code "129") (name "SCK") (class "Default")
      (node (ref "IC3") (pin "11") (pinfunction "SCK_11") (pintype "input"))
      (node (ref "IC5") (pin "11") (pinfunction "SCK_11") (pintype "input"))
      (node (ref "JP9") (pin "3") (pinfunction "3_3") (pintype "passive"))
      (node (ref "R19") (pin "1") (pinfunction "1_1") (pintype "passive"))
      (node (ref "U$1") (pin "PB3") (pinfunction "PB3_PB3") (pintype "bidirectional"))
    )
    (net (code "130") (name "SCK2") (class "Default")
      (node (ref "IC1") (pin "7") (pinfunction "CLK_7") (pintype "input"))
      (node (ref "IC4") (pin "7") (pinfunction "CLK_7") (pintype "input"))
      (node (ref "U$1") (pin "PB10") (pinfunction "PB10_PB10") (pintype "bidirectional"))
    )
    (net (code "131") (name "SLNK1") (class "Default")
      (node (ref "IC3") (pin "14") (pinfunction "SER_14") (pintype "input"))
      (node (ref "IC5") (pin "9") (pinfunction "QH*_9") (pintype "tri_state"))
      (node (ref "SJ17") (pin "P$1") (pinfunction "1_P$1") (pintype "passive"))
    )
    (net (code "132") (name "SLNK2") (class "Default")
      (node (ref "IC3") (pin "9") (pinfunction "QH*_9") (pintype "tri_state"))
      (node (ref "SJ16") (pin "P$1") (pinfunction "1_P$1") (pintype "passive"))
    )
    (net (code "133") (name "SLNK3") (class "Default")
      (node (ref "IC1") (pin "13") (pinfunction "QH_13") (pintype "output"))
      (node (ref "IC4") (pin "1") (pinfunction "SER_1") (pintype "input"))
    )
    (net (code "134") (name "SRV1") (class "Default")
      (node (ref "JP7") (pin "2") (pinfunction "2_2") (pintype "passive"))
      (node (ref "R25") (pin "2") (pinfunction "2_2") (pintype "passive"))
      (node (ref "U$1") (pin "PC9") (pinfunction "PC9_PC9") (pintype "bidirectional"))
    )
    (net (code "135") (name "SRV2") (class "Default")
      (node (ref "JP7") (pin "1") (pinfunction "1_1") (pintype "passive"))
      (node (ref "R24") (pin "2") (pinfunction "2_2") (pintype "passive"))
      (node (ref "U$1") (pin "PC7") (pinfunction "PC7_PC7") (pintype "bidirectional"))
    )
    (net (code "136") (name "SRV3") (class "Default")
      (node (ref "JP11") (pin "2") (pinfunction "2_2") (pintype "passive"))
      (node (ref "R26") (pin "2") (pinfunction "2_2") (pintype "passive"))
      (node (ref "U$1") (pin "PC8") (pinfunction "PC8_PC8") (pintype "bidirectional"))
    )
    (net (code "137") (name "SRV4") (class "Default")
      (node (ref "JP11") (pin "1") (pinfunction "1_1") (pintype "passive"))
      (node (ref "R27") (pin "2") (pinfunction "2_2") (pintype "passive"))
      (node (ref "U$1") (pin "PC6") (pinfunction "PC6_PC6") (pintype "bidirectional"))
    )
    (net (code "138") (name "SRV5") (class "Default")
      (node (ref "JP12") (pin "2") (pinfunction "2_2") (pintype "passive"))
      (node (ref "R64") (pin "2") (pinfunction "2_2") (pintype "passive"))
      (node (ref "U$1") (pin "PF1-PH1") (pinfunction "PF1-PH1_PF1-PH1") (pintype "bidirectional"))
    )
    (net (code "139") (name "SRV6") (class "Default")
      (node (ref "JP12") (pin "1") (pinfunction "1_1") (pintype "passive"))
      (node (ref "R65") (pin "2") (pinfunction "2_2") (pintype "passive"))
      (node (ref "U$1") (pin "PA15") (pinfunction "PA15_PA15") (pintype "bidirectional"))
    )
    (net (code "140") (name "SRV7") (class "Default")
      (node (ref "JP16") (pin "2") (pinfunction "2_2") (pintype "passive"))
      (node (ref "R66") (pin "2") (pinfunction "2_2") (pintype "passive"))
      (node (ref "U$1") (pin "PC12") (pinfunction "PC12_PC12") (pintype "bidirectional"))
    )
    (net (code "141") (name "SRV8") (class "Default")
      (node (ref "JP16") (pin "1") (pinfunction "1_1") (pintype "passive"))
      (node (ref "R67") (pin "2") (pinfunction "2_2") (pintype "passive"))
      (node (ref "U$1") (pin "PD2") (pinfunction "PD2_PD2") (pintype "bidirectional"))
    )
    (net (code "142") (name "TIN1") (class "Default")
      (node (ref "IC9") (pin "3") (pinfunction "+IN_3") (pintype "input"))
      (node (ref "U$1") (pin "PB2") (pinfunction "PB2_PB2") (pintype "bidirectional"))
      (node (ref "U$3") (pin "4") (pinfunction "I_4") (pintype "input"))
    )
    (net (code "143") (name "TIN2") (class "Default")
      (node (ref "IC9") (pin "5") (pinfunction "+IN_5") (pintype "input"))
      (node (ref "U$1") (pin "PB1") (pinfunction "PB1_PB1") (pintype "bidirectional"))
      (node (ref "U$2") (pin "2") (pinfunction "I_2") (pintype "input"))
    )
    (net (code "144") (name "TIN3") (class "Default")
      (node (ref "IC9") (pin "10") (pinfunction "+IN_10") (pintype "input"))
      (node (ref "U$1") (pin "PB15") (pinfunction "PB15_PB15") (pintype "bidirectional"))
      (node (ref "U$2") (pin "4") (pinfunction "I_4") (pintype "input"))
    )
    (net (code "145") (name "TIN4") (class "Default")
      (node (ref "IC9") (pin "12") (pinfunction "+IN_12") (pintype "input"))
      (node (ref "U$1") (pin "PB12") (pinfunction "PB12_PB12") (pintype "bidirectional"))
      (node (ref "U$3") (pin "2") (pinfunction "I_2") (pintype "input"))
    )
    (net (code "146") (name "TIN5") (class "Default")
      (node (ref "IC6") (pin "3") (pinfunction "+IN_3") (pintype "input"))
      (node (ref "U$1") (pin "PA4") (pinfunction "PA4_PA4") (pintype "bidirectional"))
      (node (ref "U$5") (pin "4") (pinfunction "I_4") (pintype "input"))
    )
    (net (code "147") (name "TIN6") (class "Default")
      (node (ref "IC6") (pin "5") (pinfunction "+IN_5") (pintype "input"))
      (node (ref "U$1") (pin "PC0") (pinfunction "PC0_PC0") (pintype "bidirectional"))
      (node (ref "U$4") (pin "2") (pinfunction "I_2") (pintype "input"))
    )
    (net (code "148") (name "TIN7") (class "Default")
      (node (ref "IC6") (pin "10") (pinfunction "+IN_10") (pintype "input"))
      (node (ref "U$1") (pin "PC3") (pinfunction "PC3_PC3") (pintype "bidirectional"))
      (node (ref "U$4") (pin "4") (pinfunction "I_4") (pintype "input"))
    )
    (net (code "149") (name "TIN8") (class "Default")
      (node (ref "IC6") (pin "12") (pinfunction "+IN_12") (pintype "input"))
      (node (ref "U$1") (pin "PA0") (pinfunction "PA0_PA0") (pintype "bidirectional"))
      (node (ref "U$5") (pin "2") (pinfunction "I_2") (pintype "input"))
    )
    (net (code "150") (name "V+") (class "Default")
      (node (ref "AP1509") (pin "3") (pinfunction "FB_3") (pintype "bidirectional"))
      (node (ref "C1") (pin "1") (pinfunction "1_1") (pintype "passive"))
      (node (ref "C2") (pin "+") (pinfunction "+_+") (pintype "passive"))
      (node (ref "IC10") (pin "1") (pinfunction "FB_1") (pintype "input"))
      (node (ref "L1") (pin "1") (pinfunction "1_1") (pintype "passive"))
      (node (ref "U$1") (pin "E5V") (pinfunction "E5V_E5V") (pintype "power_in"))
    )
    (net (code "151") (name "unconnected-(H1-MOUNT-PadB3,3)") (class "Default")
      (node (ref "H1") (pin "B3,3") (pinfunction "MOUNT_B3,3") (pintype "passive"))
    )
    (net (code "152") (name "unconnected-(H2-MOUNT-PadB3,3)") (class "Default")
      (node (ref "H2") (pin "B3,3") (pinfunction "MOUNT_B3,3") (pintype "passive"))
    )
    (net (code "153") (name "unconnected-(H3-MOUNT-PadB3,3)") (class "Default")
      (node (ref "H3") (pin "B3,3") (pinfunction "MOUNT_B3,3") (pintype "passive"))
    )
    (net (code "154") (name "unconnected-(H4-MOUNT-PadB3,3)") (class "Default")
      (node (ref "H4") (pin "B3,3") (pinfunction "MOUNT_B3,3") (pintype "passive"))
    )
    (net (code "155") (name "unconnected-(J3-Pad2)") (class "Default")
      (node (ref "J3") (pin "2") (pinfunction "2_2") (pintype "passive"))
    )
    (net (code "156") (name "unconnected-(U$1-PadBOOT0)") (class "Default")
      (node (ref "U$1") (pin "BOOT0") (pinfunction "BOOT0_BOOT0") (pintype "bidirectional"))
    )
    (net (code "157") (name "unconnected-(U$1-PadIOREF2)") (class "Default")
      (node (ref "U$1") (pin "IOREF2") (pinfunction "IOREF2_IOREF2") (pintype "input"))
    )
    (net (code "158") (name "unconnected-(U$1-PadNC1-PF7)") (class "Default")
      (node (ref "U$1") (pin "NC1-PF7") (pinfunction "NC1-PF7_NC1-PF7") (pintype "bidirectional"))
    )
    (net (code "159") (name "unconnected-(U$1-PadNC2-PF6)") (class "Default")
      (node (ref "U$1") (pin "NC2-PF6") (pinfunction "NC2-PF6_NC2-PF6") (pintype "bidirectional"))
    )
    (net (code "160") (name "unconnected-(U$1-PadNC3)") (class "Default")
      (node (ref "U$1") (pin "NC3") (pinfunction "NC3_NC3") (pintype "no_connect"))
    )
    (net (code "161") (name "unconnected-(U$1-PadNC4)") (class "Default")
      (node (ref "U$1") (pin "NC4") (pinfunction "NC4_NC4") (pintype "no_connect"))
    )
    (net (code "162") (name "unconnected-(U$1-PadNC5-PD8)") (class "Default")
      (node (ref "U$1") (pin "NC5-PD8") (pinfunction "NC5-PD8_NC5-PD8") (pintype "bidirectional"))
    )
    (net (code "163") (name "unconnected-(U$1-PadNC6-PB11)") (class "Default")
      (node (ref "U$1") (pin "NC6-PB11") (pinfunction "NC6-PB11_NC6-PB11") (pintype "no_connect"))
    )
    (net (code "164") (name "unconnected-(U$1-PadNC7-PF5)") (class "Default")
      (node (ref "U$1") (pin "NC7-PF5") (pinfunction "NC7-PF5_NC7-PF5") (pintype "bidirectional"))
    )
    (net (code "165") (name "unconnected-(U$1-PadNC8-PF4)") (class "Default")
      (node (ref "U$1") (pin "NC8-PF4") (pinfunction "NC8-PF4_NC8-PF4") (pintype "bidirectional"))
    )
    (net (code "166") (name "unconnected-(U$1-PadNRESET)") (class "Default")
      (node (ref "U$1") (pin "NRESET") (pinfunction "NRESET_NRESET") (pintype "input"))
    )
    (net (code "167") (name "unconnected-(U$1-PadPA1)") (class "Default")
      (node (ref "U$1") (pin "PA1") (pinfunction "PA1_PA1") (pintype "bidirectional"))
    )
    (net (code "168") (name "unconnected-(U$1-PadPA2)") (class "Default")
      (node (ref "U$1") (pin "PA2") (pinfunction "PA2_PA2") (pintype "bidirectional"))
    )
    (net (code "169") (name "unconnected-(U$1-PadPA3)") (class "Default")
      (node (ref "U$1") (pin "PA3") (pinfunction "PA3_PA3") (pintype "bidirectional"))
    )
    (net (code "170") (name "unconnected-(U$1-PadPA5)") (class "Default")
      (node (ref "U$1") (pin "PA5") (pinfunction "PA5_PA5") (pintype "bidirectional"))
    )
    (net (code "171") (name "unconnected-(U$1-PadPA7)") (class "Default")
      (node (ref "U$1") (pin "PA7") (pinfunction "PA7_PA7") (pintype "bidirectional"))
    )
    (net (code "172") (name "unconnected-(U$1-PadPA9)") (class "Default")
      (node (ref "U$1") (pin "PA9") (pinfunction "PA9_PA9") (pintype "bidirectional"))
    )
    (net (code "173") (name "unconnected-(U$1-PadPA10)") (class "Default")
      (node (ref "U$1") (pin "PA10") (pinfunction "PA10_PA10") (pintype "bidirectional"))
    )
    (net (code "174") (name "unconnected-(U$1-PadPA11)") (class "Default")
      (node (ref "U$1") (pin "PA11") (pinfunction "PA11_PA11") (pintype "bidirectional"))
    )
    (net (code "175") (name "unconnected-(U$1-PadPA12)") (class "Default")
      (node (ref "U$1") (pin "PA12") (pinfunction "PA12_PA12") (pintype "bidirectional"))
    )
    (net (code "176") (name "unconnected-(U$1-PadPA13)") (class "Default")
      (node (ref "U$1") (pin "PA13") (pinfunction "PA13_PA13") (pintype "bidirectional"))
    )
    (net (code "177") (name "unconnected-(U$1-PadPA14)") (class "Default")
      (node (ref "U$1") (pin "PA14") (pinfunction "PA14_PA14") (pintype "bidirectional"))
    )
    (net (code "178") (name "unconnected-(U$1-PadPB0)") (class "Default")
      (node (ref "U$1") (pin "PB0") (pinfunction "PB0_PB0") (pintype "bidirectional"))
    )
    (net (code "179") (name "unconnected-(U$1-PadPB13)") (class "Default")
      (node (ref "U$1") (pin "PB13") (pinfunction "PB13_PB13") (pintype "bidirectional"))
    )
    (net (code "180") (name "unconnected-(U$1-PadPC1)") (class "Default")
      (node (ref "U$1") (pin "PC1") (pinfunction "PC1_PC1") (pintype "bidirectional"))
    )
    (net (code "181") (name "unconnected-(U$1-PadPC4)") (class "Default")
      (node (ref "U$1") (pin "PC4") (pinfunction "PC4_PC4") (pintype "bidirectional"))
    )
    (net (code "182") (name "unconnected-(U$1-PadPC5)") (class "Default")
      (node (ref "U$1") (pin "PC5") (pinfunction "PC5_PC5") (pintype "bidirectional"))
    )
    (net (code "183") (name "unconnected-(U$1-PadPC13)") (class "Default")
      (node (ref "U$1") (pin "PC13") (pinfunction "PC13_PC13") (pintype "bidirectional"))
    )
    (net (code "184") (name "unconnected-(U$1-PadPC14)") (class "Default")
      (node (ref "U$1") (pin "PC14") (pinfunction "PC14_PC14") (pintype "bidirectional"))
    )
    (net (code "185") (name "unconnected-(U$1-PadPC15)") (class "Default")
      (node (ref "U$1") (pin "PC15") (pinfunction "PC15_PC15") (pintype "bidirectional"))
    )
    (net (code "186") (name "unconnected-(U$1-PadPF0-PH0)") (class "Default")
      (node (ref "U$1") (pin "PF0-PH0") (pinfunction "PF0-PH0_PF0-PH0") (pintype "bidirectional"))
    )
  )
)
